# ADC5G_PLL.net
KiCad netlist of a schematic drawn in Altium Designer
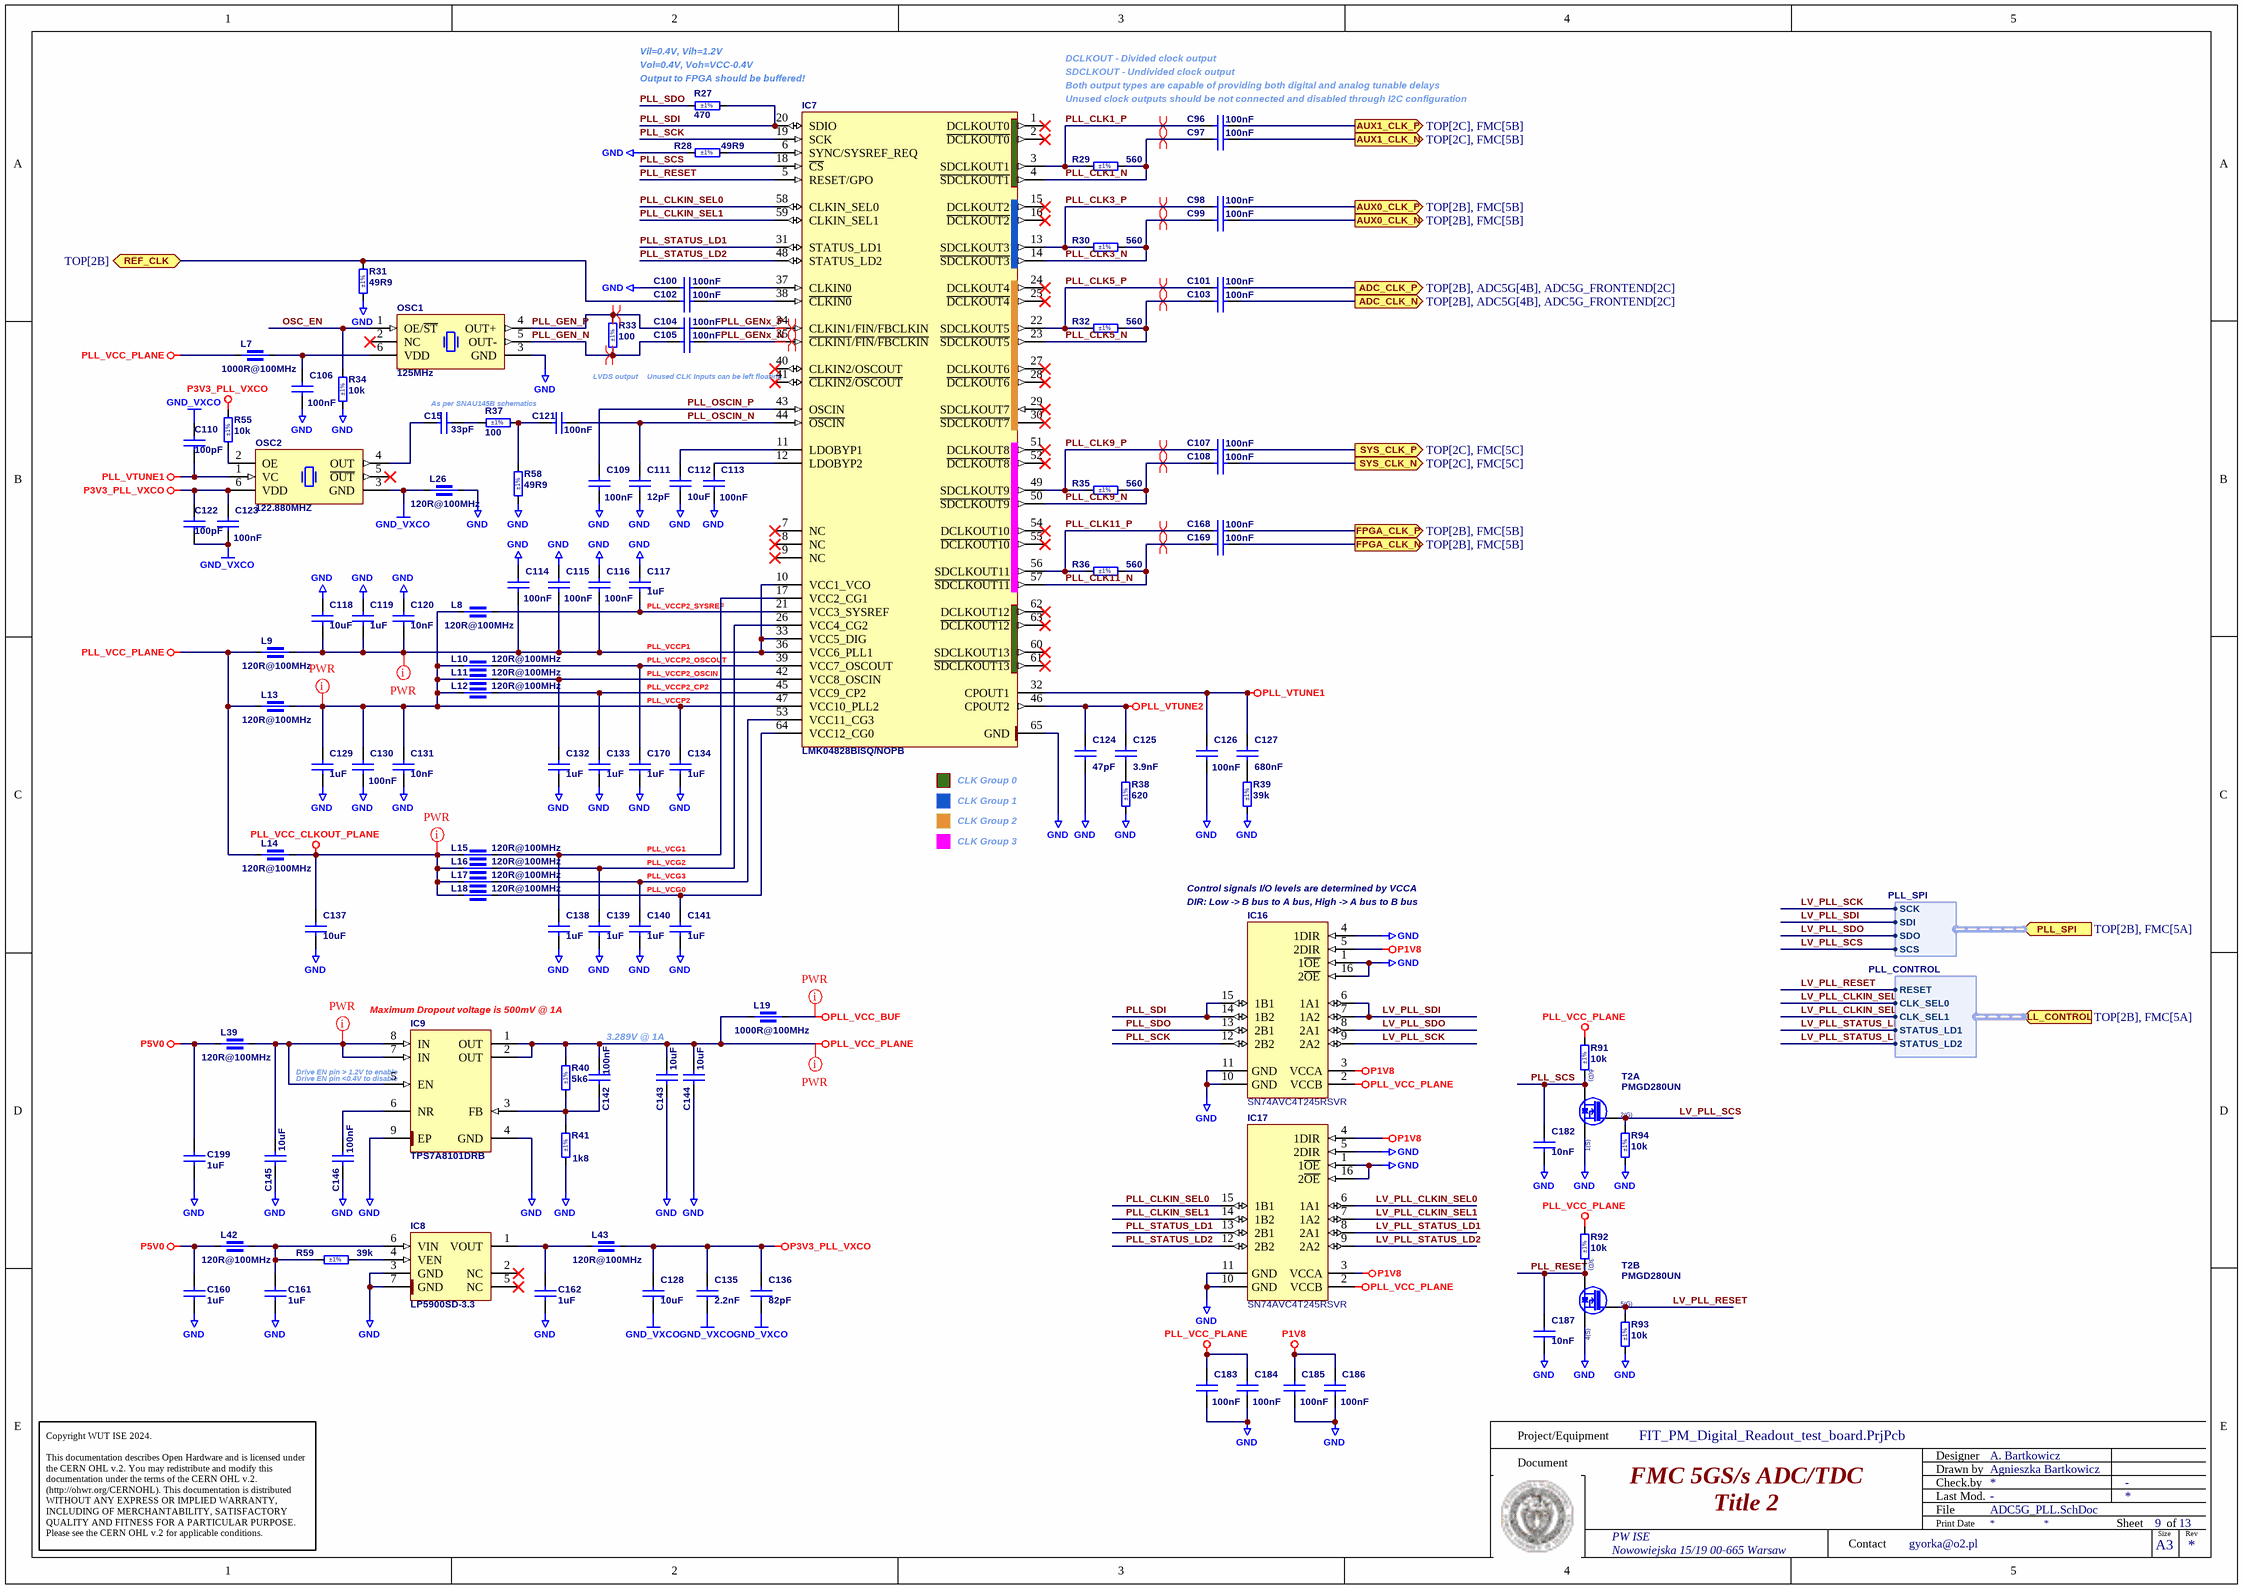
[diagram p0: ADC5G_PLL.SchDoc]

(export (version "E")
  (design (tool "Eeschema 10.0.6"))
  (components
    (comp (ref "C15")
      (value "33pF")
      (footprint "CAPC1005X61N")
      (description "Non-polarised capacitor")
      (fields
        (field (name "PART NUMBER") "CC0402_33PF_50V_1%_NP0_JOHANSON_R07S")
        (field (name "VOLTAGE") "50V")
        (field (name "AUTHOR") "CERN DEM BC")
      )
      (libsource (lib "Capacitors") (part "Capacitor - non polarized"))
    )
    (comp (ref "C96")
      (value "100nF")
      (footprint "CAPC1005X55N")
      (description "Non-polarised capacitor")
      (fields
        (field (name "PART NUMBER") "CC0402_100NF_16V_10%_X5R")
        (field (name "VOLTAGE") "16V")
        (field (name "AUTHOR") "CERN DEM JLC")
      )
      (libsource (lib "Capacitors") (part "Capacitor - non polarized"))
    )
    (comp (ref "C97")
      (value "100nF")
      (footprint "CAPC1005X55N")
      (description "Non-polarised capacitor")
      (fields
        (field (name "PART NUMBER") "CC0402_100NF_16V_10%_X5R")
        (field (name "VOLTAGE") "16V")
        (field (name "AUTHOR") "CERN DEM JLC")
      )
      (libsource (lib "Capacitors") (part "Capacitor - non polarized"))
    )
    (comp (ref "C98")
      (value "100nF")
      (footprint "CAPC1005X55N")
      (description "Non-polarised capacitor")
      (fields
        (field (name "PART NUMBER") "CC0402_100NF_16V_10%_X5R")
        (field (name "VOLTAGE") "16V")
        (field (name "AUTHOR") "CERN DEM JLC")
      )
      (libsource (lib "Capacitors") (part "Capacitor - non polarized"))
    )
    (comp (ref "C99")
      (value "100nF")
      (footprint "CAPC1005X55N")
      (description "Non-polarised capacitor")
      (fields
        (field (name "PART NUMBER") "CC0402_100NF_16V_10%_X5R")
        (field (name "VOLTAGE") "16V")
        (field (name "AUTHOR") "CERN DEM JLC")
      )
      (libsource (lib "Capacitors") (part "Capacitor - non polarized"))
    )
    (comp (ref "C100")
      (value "100nF")
      (footprint "CAPC1005X55N")
      (description "Non-polarised capacitor")
      (fields
        (field (name "PART NUMBER") "CC0402_100NF_16V_10%_X5R")
        (field (name "VOLTAGE") "16V")
        (field (name "AUTHOR") "CERN DEM JLC")
      )
      (libsource (lib "Capacitors") (part "Capacitor - non polarized"))
    )
    (comp (ref "C101")
      (value "100nF")
      (footprint "CAPC1005X55N")
      (description "Non-polarised capacitor")
      (fields
        (field (name "PART NUMBER") "CC0402_100NF_16V_10%_X5R")
        (field (name "VOLTAGE") "16V")
        (field (name "AUTHOR") "CERN DEM JLC")
      )
      (libsource (lib "Capacitors") (part "Capacitor - non polarized"))
    )
    (comp (ref "C102")
      (value "100nF")
      (footprint "CAPC1005X55N")
      (description "Non-polarised capacitor")
      (fields
        (field (name "PART NUMBER") "CC0402_100NF_16V_10%_X5R")
        (field (name "VOLTAGE") "16V")
        (field (name "AUTHOR") "CERN DEM JLC")
      )
      (libsource (lib "Capacitors") (part "Capacitor - non polarized"))
    )
    (comp (ref "C103")
      (value "100nF")
      (footprint "CAPC1005X55N")
      (description "Non-polarised capacitor")
      (fields
        (field (name "PART NUMBER") "CC0402_100NF_16V_10%_X5R")
        (field (name "VOLTAGE") "16V")
        (field (name "AUTHOR") "CERN DEM JLC")
      )
      (libsource (lib "Capacitors") (part "Capacitor - non polarized"))
    )
    (comp (ref "C104")
      (value "100nF")
      (footprint "CAPC1005X55N")
      (description "Non-polarised capacitor")
      (fields
        (field (name "PART NUMBER") "CC0402_100NF_16V_10%_X5R")
        (field (name "VOLTAGE") "16V")
        (field (name "AUTHOR") "CERN DEM JLC")
      )
      (libsource (lib "Capacitors") (part "Capacitor - non polarized"))
    )
    (comp (ref "C105")
      (value "100nF")
      (footprint "CAPC1005X55N")
      (description "Non-polarised capacitor")
      (fields
        (field (name "PART NUMBER") "CC0402_100NF_16V_10%_X5R")
        (field (name "VOLTAGE") "16V")
        (field (name "AUTHOR") "CERN DEM JLC")
      )
      (libsource (lib "Capacitors") (part "Capacitor - non polarized"))
    )
    (comp (ref "C106")
      (value "100nF")
      (footprint "CAPC1005X55N")
      (description "Non-polarised capacitor")
      (fields
        (field (name "PART NUMBER") "CC0402_100NF_16V_10%_X5R")
        (field (name "VOLTAGE") "16V")
        (field (name "AUTHOR") "CERN DEM JLC")
      )
      (libsource (lib "Capacitors") (part "Capacitor - non polarized"))
    )
    (comp (ref "C107")
      (value "100nF")
      (footprint "CAPC1005X55N")
      (description "Non-polarised capacitor")
      (fields
        (field (name "PART NUMBER") "CC0402_100NF_16V_10%_X5R")
        (field (name "VOLTAGE") "16V")
        (field (name "AUTHOR") "CERN DEM JLC")
      )
      (libsource (lib "Capacitors") (part "Capacitor - non polarized"))
    )
    (comp (ref "C108")
      (value "100nF")
      (footprint "CAPC1005X55N")
      (description "Non-polarised capacitor")
      (fields
        (field (name "PART NUMBER") "CC0402_100NF_16V_10%_X5R")
        (field (name "VOLTAGE") "16V")
        (field (name "AUTHOR") "CERN DEM JLC")
      )
      (libsource (lib "Capacitors") (part "Capacitor - non polarized"))
    )
    (comp (ref "C109")
      (value "100nF")
      (footprint "CAPC1005X55N")
      (description "Non-polarised capacitor")
      (fields
        (field (name "PART NUMBER") "CC0402_100NF_16V_10%_X5R")
        (field (name "VOLTAGE") "16V")
        (field (name "AUTHOR") "CERN DEM JLC")
      )
      (libsource (lib "Capacitors") (part "Capacitor - non polarized"))
    )
    (comp (ref "C110")
      (value "100pF")
      (footprint "CAPC1005X55N")
      (description "Non-polarised capacitor")
      (fields
        (field (name "PART NUMBER") "CC0402_100PF_25V_1%_C0G")
        (field (name "VOLTAGE") "25V")
        (field (name "AUTHOR") "CERN DEM HF")
      )
      (libsource (lib "Capacitors") (part "Capacitor - non polarized"))
    )
    (comp (ref "C111")
      (value "12pF")
      (footprint "CAPC1005X61N")
      (description "Non-polarised capacitor")
      (fields
        (field (name "PART NUMBER") "CC0402_12PF_50V_1%_NP0_JOHANSON_R07S")
        (field (name "VOLTAGE") "50V")
        (field (name "AUTHOR") "CERN DEM BC")
      )
      (libsource (lib "Capacitors") (part "Capacitor - non polarized"))
    )
    (comp (ref "C112")
      (value "10uF")
      (footprint "CAPC1608X90N")
      (description "Non-polarised capacitor")
      (fields
        (field (name "PART NUMBER") "CC0603_10UF_16V_10%_X5R_MURATA_GRT188R61C106KE13")
        (field (name "VOLTAGE") "16V")
        (field (name "AUTHOR") "CERN DEM HF")
      )
      (libsource (lib "Capacitors") (part "Capacitor - non polarized"))
    )
    (comp (ref "C113")
      (value "100nF")
      (footprint "CAPC1005X55N")
      (description "Non-polarised capacitor")
      (fields
        (field (name "PART NUMBER") "CC0402_100NF_16V_10%_X5R")
        (field (name "VOLTAGE") "16V")
        (field (name "AUTHOR") "CERN DEM JLC")
      )
      (libsource (lib "Capacitors") (part "Capacitor - non polarized"))
    )
    (comp (ref "C114")
      (value "100nF")
      (footprint "CAPC1005X55N")
      (description "Non-polarised capacitor")
      (fields
        (field (name "PART NUMBER") "CC0402_100NF_16V_10%_X5R")
        (field (name "VOLTAGE") "16V")
        (field (name "AUTHOR") "CERN DEM JLC")
      )
      (libsource (lib "Capacitors") (part "Capacitor - non polarized"))
    )
    (comp (ref "C115")
      (value "100nF")
      (footprint "CAPC1005X55N")
      (description "Non-polarised capacitor")
      (fields
        (field (name "PART NUMBER") "CC0402_100NF_16V_10%_X5R")
        (field (name "VOLTAGE") "16V")
        (field (name "AUTHOR") "CERN DEM JLC")
      )
      (libsource (lib "Capacitors") (part "Capacitor - non polarized"))
    )
    (comp (ref "C116")
      (value "100nF")
      (footprint "CAPC1005X55N")
      (description "Non-polarised capacitor")
      (fields
        (field (name "PART NUMBER") "CC0402_100NF_16V_10%_X5R")
        (field (name "VOLTAGE") "16V")
        (field (name "AUTHOR") "CERN DEM JLC")
      )
      (libsource (lib "Capacitors") (part "Capacitor - non polarized"))
    )
    (comp (ref "C117")
      (value "1uF")
      (footprint "CAPC1005X55N")
      (description "Non-polarised capacitor")
      (fields
        (field (name "PART NUMBER") "CC0402_1UF_16V_10%_X5R")
        (field (name "VOLTAGE") "16V")
        (field (name "AUTHOR") "CERN DEM JLC")
      )
      (libsource (lib "Capacitors") (part "Capacitor - non polarized"))
    )
    (comp (ref "C118")
      (value "10uF")
      (footprint "CAPC1608X90N")
      (description "Non-polarised capacitor")
      (fields
        (field (name "PART NUMBER") "CC0603_10UF_16V_10%_X5R_MURATA_GRT188R61C106KE13")
        (field (name "VOLTAGE") "16V")
        (field (name "AUTHOR") "CERN DEM HF")
      )
      (libsource (lib "Capacitors") (part "Capacitor - non polarized"))
    )
    (comp (ref "C119")
      (value "1uF")
      (footprint "CAPC1005X55N")
      (description "Non-polarised capacitor")
      (fields
        (field (name "PART NUMBER") "CC0402_1UF_16V_10%_X5R")
        (field (name "VOLTAGE") "16V")
        (field (name "AUTHOR") "CERN DEM JLC")
      )
      (libsource (lib "Capacitors") (part "Capacitor - non polarized"))
    )
    (comp (ref "C120")
      (value "10nF")
      (footprint "CAPC1005X55N")
      (description "Non-polarised capacitor")
      (fields
        (field (name "PART NUMBER") "CC0402_10NF_50V_10%_X7R")
        (field (name "VOLTAGE") "50V")
        (field (name "AUTHOR") "CERN DEM MR")
      )
      (libsource (lib "Capacitors") (part "Capacitor - non polarized"))
    )
    (comp (ref "C121")
      (value "100nF")
      (footprint "CAPC1005X55N")
      (description "Non-polarised capacitor")
      (fields
        (field (name "PART NUMBER") "CC0402_100NF_16V_10%_X5R")
        (field (name "VOLTAGE") "16V")
        (field (name "AUTHOR") "CERN DEM JLC")
      )
      (libsource (lib "Capacitors") (part "Capacitor - non polarized"))
    )
    (comp (ref "C122")
      (value "100pF")
      (footprint "CAPC1005X55N")
      (description "Non-polarised capacitor")
      (fields
        (field (name "PART NUMBER") "CC0402_100PF_25V_1%_C0G")
        (field (name "VOLTAGE") "25V")
        (field (name "AUTHOR") "CERN DEM HF")
      )
      (libsource (lib "Capacitors") (part "Capacitor - non polarized"))
    )
    (comp (ref "C123")
      (value "100nF")
      (footprint "CAPC1005X55N")
      (description "Non-polarised capacitor")
      (fields
        (field (name "PART NUMBER") "CC0402_100NF_16V_10%_X5R")
        (field (name "VOLTAGE") "16V")
        (field (name "AUTHOR") "CERN DEM JLC")
      )
      (libsource (lib "Capacitors") (part "Capacitor - non polarized"))
    )
    (comp (ref "C124")
      (value "47pF")
      (footprint "CAPC1005X55N")
      (description "Non-polarised capacitor")
      (fields
        (field (name "PART NUMBER") "CC0402_47PF_50V_1%_C0G_MURATA_GJM1555C1H470FB01D")
        (field (name "VOLTAGE") "50V")
        (field (name "AUTHOR") "CERN DEM BC")
      )
      (libsource (lib "Capacitors") (part "Capacitor - non polarized"))
    )
    (comp (ref "C125")
      (value "3.9nF")
      (footprint "CAPC1005X55N")
      (description "Non-polarised capacitor")
      (fields
        (field (name "PART NUMBER") "CC0402_3.9NF_50V_5%_X7R")
        (field (name "VOLTAGE") "50V")
        (field (name "AUTHOR") "CERN DEM BC")
      )
      (libsource (lib "Capacitors") (part "Capacitor - non polarized"))
    )
    (comp (ref "C126")
      (value "100nF")
      (footprint "CAPC1005X55N")
      (description "Non-polarised capacitor")
      (fields
        (field (name "PART NUMBER") "CC0402_100NF_16V_10%_X5R")
        (field (name "VOLTAGE") "16V")
        (field (name "AUTHOR") "CERN DEM JLC")
      )
      (libsource (lib "Capacitors") (part "Capacitor - non polarized"))
    )
    (comp (ref "C127")
      (value "680nF")
      (footprint "CAPC1005X55N")
      (description "Non-polarised capacitor")
      (fields
        (field (name "PART NUMBER") "CC0402_680NF_10V_10%_X5R")
        (field (name "VOLTAGE") "10V")
        (field (name "AUTHOR") "CERN DEM BC")
      )
      (libsource (lib "Capacitors") (part "Capacitor - non polarized"))
    )
    (comp (ref "C128")
      (value "10uF")
      (footprint "CAPC1608X90N")
      (description "Non-polarised capacitor")
      (fields
        (field (name "PART NUMBER") "CC0603_10UF_16V_10%_X5R_MURATA_GRT188R61C106KE13")
        (field (name "VOLTAGE") "16V")
        (field (name "AUTHOR") "CERN DEM HF")
      )
      (libsource (lib "Capacitors") (part "Capacitor - non polarized"))
    )
    (comp (ref "C129")
      (value "1uF")
      (footprint "CAPC1005X55N")
      (description "Non-polarised capacitor")
      (fields
        (field (name "PART NUMBER") "CC0402_1UF_16V_10%_X5R")
        (field (name "VOLTAGE") "16V")
        (field (name "AUTHOR") "CERN DEM JLC")
      )
      (libsource (lib "Capacitors") (part "Capacitor - non polarized"))
    )
    (comp (ref "C130")
      (value "100nF")
      (footprint "CAPC1005X55N")
      (description "Non-polarised capacitor")
      (fields
        (field (name "PART NUMBER") "CC0402_100NF_16V_10%_X5R")
        (field (name "VOLTAGE") "16V")
        (field (name "AUTHOR") "CERN DEM JLC")
      )
      (libsource (lib "Capacitors") (part "Capacitor - non polarized"))
    )
    (comp (ref "C131")
      (value "10nF")
      (footprint "CAPC1005X55N")
      (description "Non-polarised capacitor")
      (fields
        (field (name "PART NUMBER") "CC0402_10NF_50V_10%_X7R")
        (field (name "VOLTAGE") "50V")
        (field (name "AUTHOR") "CERN DEM MR")
      )
      (libsource (lib "Capacitors") (part "Capacitor - non polarized"))
    )
    (comp (ref "C132")
      (value "1uF")
      (footprint "CAPC1005X55N")
      (description "Non-polarised capacitor")
      (fields
        (field (name "PART NUMBER") "CC0402_1UF_16V_10%_X5R")
        (field (name "VOLTAGE") "16V")
        (field (name "AUTHOR") "CERN DEM JLC")
      )
      (libsource (lib "Capacitors") (part "Capacitor - non polarized"))
    )
    (comp (ref "C133")
      (value "1uF")
      (footprint "CAPC1005X55N")
      (description "Non-polarised capacitor")
      (fields
        (field (name "PART NUMBER") "CC0402_1UF_16V_10%_X5R")
        (field (name "VOLTAGE") "16V")
        (field (name "AUTHOR") "CERN DEM JLC")
      )
      (libsource (lib "Capacitors") (part "Capacitor - non polarized"))
    )
    (comp (ref "C134")
      (value "1uF")
      (footprint "CAPC1005X55N")
      (description "Non-polarised capacitor")
      (fields
        (field (name "PART NUMBER") "CC0402_1UF_16V_10%_X5R")
        (field (name "VOLTAGE") "16V")
        (field (name "AUTHOR") "CERN DEM JLC")
      )
      (libsource (lib "Capacitors") (part "Capacitor - non polarized"))
    )
    (comp (ref "C135")
      (value "2.2nF")
      (footprint "CAPC1005X55N")
      (description "Non-polarised capacitor")
      (fields
        (field (name "PART NUMBER") "CC0402_2.2NF_50V_10%_X7R")
        (field (name "VOLTAGE") "50V")
        (field (name "AUTHOR") "CERN DEM JLC")
      )
      (libsource (lib "Capacitors") (part "Capacitor - non polarized"))
    )
    (comp (ref "C136")
      (value "82pF")
      (footprint "CAPC1005X55N")
      (description "Non-polarised capacitor")
      (fields
        (field (name "PART NUMBER") "CC0402_82PF_25V_1%_C0G_KEMET_HiQ-CBR")
        (field (name "VOLTAGE") "25V")
        (field (name "AUTHOR") "CERN DEM MR")
      )
      (libsource (lib "Capacitors") (part "Capacitor - non polarized"))
    )
    (comp (ref "C137")
      (value "10uF")
      (footprint "CAPC1608X90N")
      (description "Non-polarised capacitor")
      (fields
        (field (name "PART NUMBER") "CC0603_10UF_16V_10%_X5R_MURATA_GRT188R61C106KE13")
        (field (name "VOLTAGE") "16V")
        (field (name "AUTHOR") "CERN DEM HF")
      )
      (libsource (lib "Capacitors") (part "Capacitor - non polarized"))
    )
    (comp (ref "C138")
      (value "1uF")
      (footprint "CAPC1005X55N")
      (description "Non-polarised capacitor")
      (fields
        (field (name "PART NUMBER") "CC0402_1UF_16V_10%_X5R")
        (field (name "VOLTAGE") "16V")
        (field (name "AUTHOR") "CERN DEM JLC")
      )
      (libsource (lib "Capacitors") (part "Capacitor - non polarized"))
    )
    (comp (ref "C139")
      (value "1uF")
      (footprint "CAPC1005X55N")
      (description "Non-polarised capacitor")
      (fields
        (field (name "PART NUMBER") "CC0402_1UF_16V_10%_X5R")
        (field (name "VOLTAGE") "16V")
        (field (name "AUTHOR") "CERN DEM JLC")
      )
      (libsource (lib "Capacitors") (part "Capacitor - non polarized"))
    )
    (comp (ref "C140")
      (value "1uF")
      (footprint "CAPC1005X55N")
      (description "Non-polarised capacitor")
      (fields
        (field (name "PART NUMBER") "CC0402_1UF_16V_10%_X5R")
        (field (name "VOLTAGE") "16V")
        (field (name "AUTHOR") "CERN DEM JLC")
      )
      (libsource (lib "Capacitors") (part "Capacitor - non polarized"))
    )
    (comp (ref "C141")
      (value "1uF")
      (footprint "CAPC1005X55N")
      (description "Non-polarised capacitor")
      (fields
        (field (name "PART NUMBER") "CC0402_1UF_16V_10%_X5R")
        (field (name "VOLTAGE") "16V")
        (field (name "AUTHOR") "CERN DEM JLC")
      )
      (libsource (lib "Capacitors") (part "Capacitor - non polarized"))
    )
    (comp (ref "C142")
      (value "100nF")
      (footprint "CAPC1005X55N")
      (description "Non-polarised capacitor")
      (fields
        (field (name "PART NUMBER") "CC0402_100NF_16V_10%_X5R")
        (field (name "VOLTAGE") "16V")
        (field (name "AUTHOR") "CERN DEM JLC")
      )
      (libsource (lib "Capacitors") (part "Capacitor - non polarized"))
    )
    (comp (ref "C143")
      (value "10uF")
      (footprint "CAPC1608X90N")
      (description "Non-polarised capacitor")
      (fields
        (field (name "PART NUMBER") "CC0603_10UF_16V_10%_X5R_MURATA_GRT188R61C106KE13")
        (field (name "VOLTAGE") "16V")
        (field (name "AUTHOR") "CERN DEM HF")
      )
      (libsource (lib "Capacitors") (part "Capacitor - non polarized"))
    )
    (comp (ref "C144")
      (value "10uF")
      (footprint "CAPC1608X90N")
      (description "Non-polarised capacitor")
      (fields
        (field (name "PART NUMBER") "CC0603_10UF_16V_10%_X5R_MURATA_GRT188R61C106KE13")
        (field (name "VOLTAGE") "16V")
        (field (name "AUTHOR") "CERN DEM HF")
      )
      (libsource (lib "Capacitors") (part "Capacitor - non polarized"))
    )
    (comp (ref "C145")
      (value "10uF")
      (footprint "CAPC1608X90N")
      (description "Non-polarised capacitor")
      (fields
        (field (name "PART NUMBER") "CC0603_10UF_16V_10%_X5R_MURATA_GRT188R61C106KE13")
        (field (name "VOLTAGE") "16V")
        (field (name "AUTHOR") "CERN DEM HF")
      )
      (libsource (lib "Capacitors") (part "Capacitor - non polarized"))
    )
    (comp (ref "C146")
      (value "100nF")
      (footprint "CAPC1005X55N")
      (description "Non-polarised capacitor")
      (fields
        (field (name "PART NUMBER") "CC0402_100NF_16V_10%_X5R")
        (field (name "VOLTAGE") "16V")
        (field (name "AUTHOR") "CERN DEM JLC")
      )
      (libsource (lib "Capacitors") (part "Capacitor - non polarized"))
    )
    (comp (ref "C160")
      (value "1uF")
      (footprint "CAPC1005X55N")
      (description "Non-polarised capacitor")
      (fields
        (field (name "PART NUMBER") "CC0402_1UF_16V_10%_X5R")
        (field (name "VOLTAGE") "16V")
        (field (name "AUTHOR") "CERN DEM JLC")
      )
      (libsource (lib "Capacitors") (part "Capacitor - non polarized"))
    )
    (comp (ref "C161")
      (value "1uF")
      (footprint "CAPC1005X55N")
      (description "Non-polarised capacitor")
      (fields
        (field (name "PART NUMBER") "CC0402_1UF_16V_10%_X5R")
        (field (name "VOLTAGE") "16V")
        (field (name "AUTHOR") "CERN DEM JLC")
      )
      (libsource (lib "Capacitors") (part "Capacitor - non polarized"))
    )
    (comp (ref "C162")
      (value "1uF")
      (footprint "CAPC1005X55N")
      (description "Non-polarised capacitor")
      (fields
        (field (name "PART NUMBER") "CC0402_1UF_16V_10%_X5R")
        (field (name "VOLTAGE") "16V")
        (field (name "AUTHOR") "CERN DEM JLC")
      )
      (libsource (lib "Capacitors") (part "Capacitor - non polarized"))
    )
    (comp (ref "C168")
      (value "100nF")
      (footprint "CAPC1005X55N")
      (description "Non-polarised capacitor")
      (fields
        (field (name "PART NUMBER") "CC0402_100NF_16V_10%_X5R")
        (field (name "VOLTAGE") "16V")
        (field (name "AUTHOR") "CERN DEM JLC")
      )
      (libsource (lib "Capacitors") (part "Capacitor - non polarized"))
    )
    (comp (ref "C169")
      (value "100nF")
      (footprint "CAPC1005X55N")
      (description "Non-polarised capacitor")
      (fields
        (field (name "PART NUMBER") "CC0402_100NF_16V_10%_X5R")
        (field (name "VOLTAGE") "16V")
        (field (name "AUTHOR") "CERN DEM JLC")
      )
      (libsource (lib "Capacitors") (part "Capacitor - non polarized"))
    )
    (comp (ref "C170")
      (value "1uF")
      (footprint "CAPC1005X55N")
      (description "Non-polarised capacitor")
      (fields
        (field (name "PART NUMBER") "CC0402_1UF_16V_10%_X5R")
        (field (name "VOLTAGE") "16V")
        (field (name "AUTHOR") "CERN DEM JLC")
      )
      (libsource (lib "Capacitors") (part "Capacitor - non polarized"))
    )
    (comp (ref "C182")
      (value "10nF")
      (footprint "CAPC1005X55N")
      (description "Non-polarised capacitor")
      (fields
        (field (name "PART NUMBER") "CC0402_10NF_50V_10%_X7R")
        (field (name "VOLTAGE") "50V")
        (field (name "AUTHOR") "CERN DEM MR")
      )
      (libsource (lib "Capacitors") (part "Capacitor - non polarized"))
    )
    (comp (ref "C183")
      (value "100nF")
      (footprint "CAPC1005X55N")
      (description "Non-polarised capacitor")
      (fields
        (field (name "PART NUMBER") "CC0402_100NF_16V_10%_X5R")
        (field (name "VOLTAGE") "16V")
        (field (name "AUTHOR") "CERN DEM JLC")
      )
      (libsource (lib "Capacitors") (part "Capacitor - non polarized"))
    )
    (comp (ref "C184")
      (value "100nF")
      (footprint "CAPC1005X55N")
      (description "Non-polarised capacitor")
      (fields
        (field (name "PART NUMBER") "CC0402_100NF_16V_10%_X5R")
        (field (name "VOLTAGE") "16V")
        (field (name "AUTHOR") "CERN DEM JLC")
      )
      (libsource (lib "Capacitors") (part "Capacitor - non polarized"))
    )
    (comp (ref "C185")
      (value "100nF")
      (footprint "CAPC1005X55N")
      (description "Non-polarised capacitor")
      (fields
        (field (name "PART NUMBER") "CC0402_100NF_16V_10%_X5R")
        (field (name "VOLTAGE") "16V")
        (field (name "AUTHOR") "CERN DEM JLC")
      )
      (libsource (lib "Capacitors") (part "Capacitor - non polarized"))
    )
    (comp (ref "C186")
      (value "100nF")
      (footprint "CAPC1005X55N")
      (description "Non-polarised capacitor")
      (fields
        (field (name "PART NUMBER") "CC0402_100NF_16V_10%_X5R")
        (field (name "VOLTAGE") "16V")
        (field (name "AUTHOR") "CERN DEM JLC")
      )
      (libsource (lib "Capacitors") (part "Capacitor - non polarized"))
    )
    (comp (ref "C187")
      (value "10nF")
      (footprint "CAPC1005X55N")
      (description "Non-polarised capacitor")
      (fields
        (field (name "PART NUMBER") "CC0402_10NF_50V_10%_X7R")
        (field (name "VOLTAGE") "50V")
        (field (name "AUTHOR") "CERN DEM MR")
      )
      (libsource (lib "Capacitors") (part "Capacitor - non polarized"))
    )
    (comp (ref "C199")
      (value "1uF")
      (footprint "CAPC1005X55N")
      (description "Non-polarised capacitor")
      (fields
        (field (name "PART NUMBER") "CC0402_1UF_16V_10%_X5R")
        (field (name "VOLTAGE") "16V")
        (field (name "AUTHOR") "CERN DEM JLC")
      )
      (libsource (lib "Capacitors") (part "Capacitor - non polarized"))
    )
    (comp (ref "IC7")
      (value "LMK04828BISQ/NOPB")
      (footprint "QFN50P900X900X80-65N-S730")
      (description "Ultra Low-Noise Clock Jitter Cleaner with Dual Loop PLLs")
      (fields
        (field (name "MANUFACTURER") "TEXAS INSTRUMENTS")
        (field (name "MANUFACTURER PART NUMBER") "LMK04828BISQ")
        (field (name "AUTHOR") "CERN DEM MR")
      )
      (libsource (lib "ICs And Semiconductors") (part "LMK04828"))
    )
    (comp (ref "IC8")
      (value "LP5900SD-3.3")
      (footprint "SON65P250X220X80-7N-R85X130")
      (description "Ultra Low Noise, 150 mA Linear Regulator for RF/Analog Circuits Requires No Bypass Capacitor")
      (fields (field (name "MANUFACTURER") "TEXAS INSTRUMENTS") (field (name "AUTHOR") "CERN DEM JLC"))
      (libsource (lib "ICs And Semiconductors") (part "LP5900SD"))
    )
    (comp (ref "IC9")
      (value "TPS7A8101DRB")
      (footprint "TEXAS_DRB(S-PVSON-N8)")
      (description "0.8V to 6V, 1A, Low-Noise, Wide-Bandwidth, High PSRR, Low-Dropout Linear Regulator")
      (fields (field (name "MANUFACTURER") "TEXAS INSTRUMENTS") (field (name "AUTHOR") "CERN DEM BC"))
      (libsource (lib "ICs And Semiconductors") (part "TPS7A8101DRB"))
    )
    (comp (ref "IC16")
      (value "SN74AVC4T245RSVR")
      (footprint "QFN40P180X260X55-16N")
      (description "4-Bit Dual-Supply Bus Transceiver with Configurable Voltage Translation and 3-State Output")
      (fields (field (name "MANUFACTURER") "TEXAS INSTRUMENTS") (field (name "AUTHOR") "CERN DEM JLC"))
      (libsource (lib "ICs And Semiconductors") (part "744T245_a"))
    )
    (comp (ref "IC17")
      (value "SN74AVC4T245RSVR")
      (footprint "QFN40P180X260X55-16N")
      (description "4-Bit Dual-Supply Bus Transceiver with Configurable Voltage Translation and 3-State Output")
      (fields (field (name "MANUFACTURER") "TEXAS INSTRUMENTS") (field (name "AUTHOR") "CERN DEM JLC"))
      (libsource (lib "ICs And Semiconductors") (part "744T245_a"))
    )
    (comp (ref "L7")
      (value "1000R@100MHz")
      (footprint "INDC1608X95N")
      (fields
        (field (name "PART NUMBER") "IND0603_MURATA_BLM18KG102SN1")
        (field (name "POWER") "1A")
        (field (name "TOLERANCE") "±25%")
        (field (name "AUTHOR") "CERN DEM HF")
      )
      (libsource (lib "Inductors & Transformers") (part "Ferrite Bead"))
    )
    (comp (ref "L8")
      (value "120R@100MHz")
      (footprint "INDC1005X55N")
      (fields
        (field (name "PART NUMBER") "IND0402_MURATA_BLM15PX121SN1D")
        (field (name "POWER") "2A")
        (field (name "TOLERANCE") "±25%")
        (field (name "AUTHOR") "CERN DEM JMW")
      )
      (libsource (lib "Inductors & Transformers") (part "Ferrite Bead"))
    )
    (comp (ref "L9")
      (value "120R@100MHz")
      (footprint "INDC1005X55N")
      (fields
        (field (name "PART NUMBER") "IND0402_MURATA_BLM15PX121SN1D")
        (field (name "POWER") "2A")
        (field (name "TOLERANCE") "±25%")
        (field (name "AUTHOR") "CERN DEM JMW")
      )
      (libsource (lib "Inductors & Transformers") (part "Ferrite Bead"))
    )
    (comp (ref "L10")
      (value "120R@100MHz")
      (footprint "INDC1005X55N")
      (fields
        (field (name "PART NUMBER") "IND0402_MURATA_BLM15PX121SN1D")
        (field (name "POWER") "2A")
        (field (name "TOLERANCE") "±25%")
        (field (name "AUTHOR") "CERN DEM JMW")
      )
      (libsource (lib "Inductors & Transformers") (part "Ferrite Bead"))
    )
    (comp (ref "L11")
      (value "120R@100MHz")
      (footprint "INDC1005X55N")
      (fields
        (field (name "PART NUMBER") "IND0402_MURATA_BLM15PX121SN1D")
        (field (name "POWER") "2A")
        (field (name "TOLERANCE") "±25%")
        (field (name "AUTHOR") "CERN DEM JMW")
      )
      (libsource (lib "Inductors & Transformers") (part "Ferrite Bead"))
    )
    (comp (ref "L12")
      (value "120R@100MHz")
      (footprint "INDC1005X55N")
      (fields
        (field (name "PART NUMBER") "IND0402_MURATA_BLM15PX121SN1D")
        (field (name "POWER") "2A")
        (field (name "TOLERANCE") "±25%")
        (field (name "AUTHOR") "CERN DEM JMW")
      )
      (libsource (lib "Inductors & Transformers") (part "Ferrite Bead"))
    )
    (comp (ref "L13")
      (value "120R@100MHz")
      (footprint "INDC1005X55N")
      (fields
        (field (name "PART NUMBER") "IND0402_MURATA_BLM15PX121SN1D")
        (field (name "POWER") "2A")
        (field (name "TOLERANCE") "±25%")
        (field (name "AUTHOR") "CERN DEM JMW")
      )
      (libsource (lib "Inductors & Transformers") (part "Ferrite Bead"))
    )
    (comp (ref "L14")
      (value "120R@100MHz")
      (footprint "INDC1005X55N")
      (fields
        (field (name "PART NUMBER") "IND0402_MURATA_BLM15PX121SN1D")
        (field (name "POWER") "2A")
        (field (name "TOLERANCE") "±25%")
        (field (name "AUTHOR") "CERN DEM JMW")
      )
      (libsource (lib "Inductors & Transformers") (part "Ferrite Bead"))
    )
    (comp (ref "L15")
      (value "120R@100MHz")
      (footprint "INDC1005X55N")
      (fields
        (field (name "PART NUMBER") "IND0402_MURATA_BLM15PX121SN1D")
        (field (name "POWER") "2A")
        (field (name "TOLERANCE") "±25%")
        (field (name "AUTHOR") "CERN DEM JMW")
      )
      (libsource (lib "Inductors & Transformers") (part "Ferrite Bead"))
    )
    (comp (ref "L16")
      (value "120R@100MHz")
      (footprint "INDC1005X55N")
      (fields
        (field (name "PART NUMBER") "IND0402_MURATA_BLM15PX121SN1D")
        (field (name "POWER") "2A")
        (field (name "TOLERANCE") "±25%")
        (field (name "AUTHOR") "CERN DEM JMW")
      )
      (libsource (lib "Inductors & Transformers") (part "Ferrite Bead"))
    )
    (comp (ref "L17")
      (value "120R@100MHz")
      (footprint "INDC1005X55N")
      (fields
        (field (name "PART NUMBER") "IND0402_MURATA_BLM15PX121SN1D")
        (field (name "POWER") "2A")
        (field (name "TOLERANCE") "±25%")
        (field (name "AUTHOR") "CERN DEM JMW")
      )
      (libsource (lib "Inductors & Transformers") (part "Ferrite Bead"))
    )
    (comp (ref "L18")
      (value "120R@100MHz")
      (footprint "INDC1005X55N")
      (fields
        (field (name "PART NUMBER") "IND0402_MURATA_BLM15PX121SN1D")
        (field (name "POWER") "2A")
        (field (name "TOLERANCE") "±25%")
        (field (name "AUTHOR") "CERN DEM JMW")
      )
      (libsource (lib "Inductors & Transformers") (part "Ferrite Bead"))
    )
    (comp (ref "L19")
      (value "1000R@100MHz")
      (footprint "INDC1608X95N")
      (fields
        (field (name "PART NUMBER") "IND0603_MURATA_BLM18KG102SN1")
        (field (name "POWER") "1A")
        (field (name "TOLERANCE") "±25%")
        (field (name "AUTHOR") "CERN DEM HF")
      )
      (libsource (lib "Inductors & Transformers") (part "Ferrite Bead"))
    )
    (comp (ref "L26")
      (value "120R@100MHz")
      (footprint "INDC1005X55N")
      (fields
        (field (name "PART NUMBER") "IND0402_MURATA_BLM15PX121SN1D")
        (field (name "POWER") "2A")
        (field (name "TOLERANCE") "±25%")
        (field (name "AUTHOR") "CERN DEM JMW")
      )
      (libsource (lib "Inductors & Transformers") (part "Ferrite Bead"))
    )
    (comp (ref "L39")
      (value "120R@100MHz")
      (footprint "INDC1005X55N")
      (fields
        (field (name "PART NUMBER") "IND0402_MURATA_BLM15PX121SN1D")
        (field (name "POWER") "2A")
        (field (name "TOLERANCE") "±25%")
        (field (name "AUTHOR") "CERN DEM JMW")
      )
      (libsource (lib "Inductors & Transformers") (part "Ferrite Bead"))
    )
    (comp (ref "L42")
      (value "120R@100MHz")
      (footprint "INDC1005X55N")
      (fields
        (field (name "PART NUMBER") "IND0402_MURATA_BLM15PX121SN1D")
        (field (name "POWER") "2A")
        (field (name "TOLERANCE") "±25%")
        (field (name "AUTHOR") "CERN DEM JMW")
      )
      (libsource (lib "Inductors & Transformers") (part "Ferrite Bead"))
    )
    (comp (ref "L43")
      (value "120R@100MHz")
      (footprint "INDC1005X55N")
      (fields
        (field (name "PART NUMBER") "IND0402_MURATA_BLM15PX121SN1D")
        (field (name "POWER") "2A")
        (field (name "TOLERANCE") "±25%")
        (field (name "AUTHOR") "CERN DEM JMW")
      )
      (libsource (lib "Inductors & Transformers") (part "Ferrite Bead"))
    )
    (comp (ref "OSC1")
      (value "125MHz")
      (footprint "OSC_SI-TIME_SIT9121-C")
      (description "Standard Frequency Differential Oscillator")
      (fields
        (field (name "PART NUMBER") "OSC_125MHZ_SI-TIME_SIT9121AI-2C2-33E125.000000")
        (field (name "MANUFACTURER") "SI TIME")
        (field (name "AUTHOR") "CERN DEM HF")
      )
      (libsource (lib "ICs And Semiconductors") (part "Oscillator SI-TIME_SIT9121"))
    )
    (comp (ref "OSC2")
      (value "122.880MHZ")
      (footprint "OSCSC254P500X700X190-6N")
      (description "Programmable - High Performance SMD VCXO")
      (fields
        (field (name "PART NUMBER") "OSC_122.880MHZ_ABRACON_ASG-D-V-A-122.880MHZ")
        (field (name "MANUFACTURER") "ABRACON")
        (field (name "AUTHOR") "CERN DEM HF")
      )
      (libsource (lib "ICs And Semiconductors") (part "Oscillator ABRACON_ASG-D-V"))
    )
    (comp (ref "R27")
      (value "470")
      (footprint "RESC1005X40N")
      (description "Resistor - 1%")
      (fields
        (field (name "TOLERANCE") "±1%")
        (field (name "PART NUMBER") "R0402_470R_1%_0.0625W_100PPM")
        (field (name "POWER") "0.0625W")
        (field (name "AUTHOR") "CERN DEM JLC")
      )
      (libsource (lib "Resistors") (part "Resistor - 1%"))
    )
    (comp (ref "R28")
      (value "49R9")
      (footprint "RESC1005X40N")
      (description "Resistor - 1%")
      (fields
        (field (name "TOLERANCE") "±1%")
        (field (name "PART NUMBER") "R0402_49R9_1%_0.0625W_100PPM")
        (field (name "POWER") "0.0625W")
        (field (name "AUTHOR") "CERN DEM JLC")
      )
      (libsource (lib "Resistors") (part "Resistor - 1%"))
    )
    (comp (ref "R29")
      (value "560")
      (footprint "RESC1005X40N")
      (description "Resistor - 1%")
      (fields
        (field (name "TOLERANCE") "±1%")
        (field (name "PART NUMBER") "R0402_560R_1%_0.0625W_100PPM")
        (field (name "POWER") "0.0625W")
        (field (name "AUTHOR") "CERN DEM JLC")
      )
      (libsource (lib "Resistors") (part "Resistor - 1%"))
    )
    (comp (ref "R30")
      (value "560")
      (footprint "RESC1005X40N")
      (description "Resistor - 1%")
      (fields
        (field (name "TOLERANCE") "±1%")
        (field (name "PART NUMBER") "R0402_560R_1%_0.0625W_100PPM")
        (field (name "POWER") "0.0625W")
        (field (name "AUTHOR") "CERN DEM JLC")
      )
      (libsource (lib "Resistors") (part "Resistor - 1%"))
    )
    (comp (ref "R31")
      (value "49R9")
      (footprint "RESC1005X40N")
      (description "Resistor - 1%")
      (fields
        (field (name "TOLERANCE") "±1%")
        (field (name "PART NUMBER") "R0402_49R9_1%_0.0625W_100PPM")
        (field (name "POWER") "0.0625W")
        (field (name "AUTHOR") "CERN DEM JLC")
      )
      (libsource (lib "Resistors") (part "Resistor - 1%"))
    )
    (comp (ref "R32")
      (value "560")
      (footprint "RESC1005X40N")
      (description "Resistor - 1%")
      (fields
        (field (name "TOLERANCE") "±1%")
        (field (name "PART NUMBER") "R0402_560R_1%_0.0625W_100PPM")
        (field (name "POWER") "0.0625W")
        (field (name "AUTHOR") "CERN DEM JLC")
      )
      (libsource (lib "Resistors") (part "Resistor - 1%"))
    )
    (comp (ref "R33")
      (value "100")
      (footprint "RESC1005X40N")
      (description "Resistor - 1%")
      (fields
        (field (name "TOLERANCE") "±1%")
        (field (name "PART NUMBER") "R0402_100R_1%_0.0625W_100PPM")
        (field (name "POWER") "0.0625W")
        (field (name "AUTHOR") "CERN DEM JLC")
      )
      (libsource (lib "Resistors") (part "Resistor - 1%"))
    )
    (comp (ref "R34")
      (value "10k")
      (footprint "RESC1005X40N")
      (description "Resistor - 1%")
      (fields
        (field (name "TOLERANCE") "±1%")
        (field (name "PART NUMBER") "R0402_10K_1%_0.0625W_100PPM")
        (field (name "POWER") "0.0625W")
        (field (name "AUTHOR") "CERN DEM JLC")
      )
      (libsource (lib "Resistors") (part "Resistor - 1%"))
    )
    (comp (ref "R35")
      (value "560")
      (footprint "RESC1005X40N")
      (description "Resistor - 1%")
      (fields
        (field (name "TOLERANCE") "±1%")
        (field (name "PART NUMBER") "R0402_560R_1%_0.0625W_100PPM")
        (field (name "POWER") "0.0625W")
        (field (name "AUTHOR") "CERN DEM JLC")
      )
      (libsource (lib "Resistors") (part "Resistor - 1%"))
    )
    (comp (ref "R36")
      (value "560")
      (footprint "RESC1005X40N")
      (description "Resistor - 1%")
      (fields
        (field (name "TOLERANCE") "±1%")
        (field (name "PART NUMBER") "R0402_560R_1%_0.0625W_100PPM")
        (field (name "POWER") "0.0625W")
        (field (name "AUTHOR") "CERN DEM JLC")
      )
      (libsource (lib "Resistors") (part "Resistor - 1%"))
    )
    (comp (ref "R37")
      (value "100")
      (footprint "RESC1005X40N")
      (description "Resistor - 1%")
      (fields
        (field (name "TOLERANCE") "±1%")
        (field (name "PART NUMBER") "R0402_100R_1%_0.0625W_100PPM")
        (field (name "POWER") "0.0625W")
        (field (name "AUTHOR") "CERN DEM JLC")
      )
      (libsource (lib "Resistors") (part "Resistor - 1%"))
    )
    (comp (ref "R38")
      (value "620")
      (footprint "RESC1005X40N")
      (description "Resistor - 1%")
      (fields
        (field (name "TOLERANCE") "±1%")
        (field (name "PART NUMBER") "R0402_620R_1%_0.0625W_100PPM")
        (field (name "POWER") "0.0625W")
        (field (name "AUTHOR") "CERN DEM JLC")
      )
      (libsource (lib "Resistors") (part "Resistor - 1%"))
    )
    (comp (ref "R39")
      (value "39k")
      (footprint "RESC1005X40N")
      (description "Resistor - 1%")
      (fields
        (field (name "TOLERANCE") "±1%")
        (field (name "PART NUMBER") "R0402_39K_1%_0.0625W_100PPM")
        (field (name "POWER") "0.0625W")
        (field (name "AUTHOR") "CERN DEM JLC")
      )
      (libsource (lib "Resistors") (part "Resistor - 1%"))
    )
    (comp (ref "R40")
      (value "5k6")
      (footprint "RESC1005X40N")
      (description "Resistor - 1%")
      (fields
        (field (name "TOLERANCE") "±1%")
        (field (name "PART NUMBER") "R0402_5K6_1%_0.0625W_100PPM")
        (field (name "POWER") "0.0625W")
        (field (name "AUTHOR") "CERN DEM JLC")
      )
      (libsource (lib "Resistors") (part "Resistor - 1%"))
    )
    (comp (ref "R41")
      (value "1k8")
      (footprint "RESC1005X40N")
      (description "Resistor - 1%")
      (fields
        (field (name "TOLERANCE") "±1%")
        (field (name "PART NUMBER") "R0402_1K8_1%_0.0625W_100PPM")
        (field (name "POWER") "0.0625W")
        (field (name "AUTHOR") "CERN DEM JLC")
      )
      (libsource (lib "Resistors") (part "Resistor - 1%"))
    )
    (comp (ref "R55")
      (value "10k")
      (footprint "RESC1005X40N")
      (description "Resistor - 1%")
      (fields
        (field (name "TOLERANCE") "±1%")
        (field (name "PART NUMBER") "R0402_10K_1%_0.0625W_100PPM")
        (field (name "POWER") "0.0625W")
        (field (name "AUTHOR") "CERN DEM JLC")
      )
      (libsource (lib "Resistors") (part "Resistor - 1%"))
    )
    (comp (ref "R58")
      (value "49R9")
      (footprint "RESC1005X40N")
      (description "Resistor - 1%")
      (fields
        (field (name "TOLERANCE") "±1%")
        (field (name "PART NUMBER") "R0402_49R9_1%_0.0625W_100PPM")
        (field (name "POWER") "0.0625W")
        (field (name "AUTHOR") "CERN DEM JLC")
      )
      (libsource (lib "Resistors") (part "Resistor - 1%"))
    )
    (comp (ref "R59")
      (value "39k")
      (footprint "RESC1005X40N")
      (description "Resistor - 1%")
      (fields
        (field (name "TOLERANCE") "±1%")
        (field (name "PART NUMBER") "R0402_39K_1%_0.0625W_100PPM")
        (field (name "POWER") "0.0625W")
        (field (name "AUTHOR") "CERN DEM JLC")
      )
      (libsource (lib "Resistors") (part "Resistor - 1%"))
    )
    (comp (ref "R91")
      (value "10k")
      (footprint "RESC1005X40N")
      (description "Resistor - 1%")
      (fields
        (field (name "TOLERANCE") "±1%")
        (field (name "PART NUMBER") "R0402_10K_1%_0.0625W_100PPM")
        (field (name "POWER") "0.0625W")
        (field (name "AUTHOR") "CERN DEM JLC")
      )
      (libsource (lib "Resistors") (part "Resistor - 1%"))
    )
    (comp (ref "R92")
      (value "10k")
      (footprint "RESC1005X40N")
      (description "Resistor - 1%")
      (fields
        (field (name "TOLERANCE") "±1%")
        (field (name "PART NUMBER") "R0402_10K_1%_0.0625W_100PPM")
        (field (name "POWER") "0.0625W")
        (field (name "AUTHOR") "CERN DEM JLC")
      )
      (libsource (lib "Resistors") (part "Resistor - 1%"))
    )
    (comp (ref "R93")
      (value "10k")
      (footprint "RESC1005X40N")
      (description "Resistor - 1%")
      (fields
        (field (name "TOLERANCE") "±1%")
        (field (name "PART NUMBER") "R0402_10K_1%_0.0625W_100PPM")
        (field (name "POWER") "0.0625W")
        (field (name "AUTHOR") "CERN DEM JLC")
      )
      (libsource (lib "Resistors") (part "Resistor - 1%"))
    )
    (comp (ref "R94")
      (value "10k")
      (footprint "RESC1005X40N")
      (description "Resistor - 1%")
      (fields
        (field (name "TOLERANCE") "±1%")
        (field (name "PART NUMBER") "R0402_10K_1%_0.0625W_100PPM")
        (field (name "POWER") "0.0625W")
        (field (name "AUTHOR") "CERN DEM JLC")
      )
      (libsource (lib "Resistors") (part "Resistor - 1%"))
    )
    (comp (ref "T2")
      (value "PMGD280UN")
      (footprint "SOT65P210X110-6N")
      (description "Dual N-Channel micro TrenchMOS™ Ultra Low Level FET")
      (fields (field (name "MANUFACTURER") "NXP SEMICONDUCTORS") (field (name "AUTHOR") "CERN DEM JLC"))
      (libsource (lib "") (part "PMGD280UN_1"))
    )
  )
  (nets
    (net (code "3") (name "/ADC_CLK_N") (class "Default")
      (node (ref "C103") (pin "2") (pinfunction "2_2") (pintype "passive"))
    )
    (net (code "4") (name "/ADC_CLK_P") (class "Default")
      (node (ref "C101") (pin "2") (pinfunction "2_2") (pintype "passive"))
    )
    (net (code "5") (name "/AUX0_CLK_N") (class "Default")
      (node (ref "C99") (pin "2") (pinfunction "2_2") (pintype "passive"))
    )
    (net (code "6") (name "/AUX0_CLK_P") (class "Default")
      (node (ref "C98") (pin "2") (pinfunction "2_2") (pintype "passive"))
    )
    (net (code "7") (name "/AUX1_CLK_N") (class "Default")
      (node (ref "C97") (pin "2") (pinfunction "2_2") (pintype "passive"))
    )
    (net (code "8") (name "/AUX1_CLK_P") (class "Default")
      (node (ref "C96") (pin "2") (pinfunction "2_2") (pintype "passive"))
    )
    (net (code "9") (name "/FPGA_CLK_N") (class "Default")
      (node (ref "C169") (pin "2") (pinfunction "2_2") (pintype "passive"))
    )
    (net (code "10") (name "/FPGA_CLK_P") (class "Default")
      (node (ref "C168") (pin "2") (pinfunction "2_2") (pintype "passive"))
    )
    (net (code "11") (name "/LV_PLL_CLKIN_SEL0") (class "Default")
      (node (ref "IC17") (pin "6") (pinfunction "1A1_6") (pintype "bidirectional"))
    )
    (net (code "12") (name "/LV_PLL_CLKIN_SEL1") (class "Default")
      (node (ref "IC17") (pin "7") (pinfunction "1A2_7") (pintype "bidirectional"))
    )
    (net (code "13") (name "/LV_PLL_RESET") (class "Default")
      (node (ref "R93") (pin "2") (pinfunction "2_2") (pintype "passive"))
      (node (ref "T2") (pin "5") (pinfunction "G_5") (pintype "passive"))
    )
    (net (code "14") (name "/LV_PLL_SCK") (class "Default")
      (node (ref "IC16") (pin "9") (pinfunction "2A2_9") (pintype "bidirectional"))
    )
    (net (code "15") (name "/LV_PLL_SCS") (class "Default")
      (node (ref "R94") (pin "2") (pinfunction "2_2") (pintype "passive"))
      (node (ref "T2") (pin "2") (pinfunction "G_2") (pintype "passive"))
    )
    (net (code "16") (name "/LV_PLL_SDI") (class "Default")
      (node (ref "IC16") (pin "6") (pinfunction "1A1_6") (pintype "bidirectional"))
      (node (ref "IC16") (pin "7") (pinfunction "1A2_7") (pintype "bidirectional"))
    )
    (net (code "17") (name "/LV_PLL_SDO") (class "Default")
      (node (ref "IC16") (pin "8") (pinfunction "2A1_8") (pintype "bidirectional"))
    )
    (net (code "18") (name "/LV_PLL_STATUS_LD1") (class "Default")
      (node (ref "IC17") (pin "8") (pinfunction "2A1_8") (pintype "bidirectional"))
    )
    (net (code "19") (name "/LV_PLL_STATUS_LD2") (class "Default")
      (node (ref "IC17") (pin "9") (pinfunction "2A2_9") (pintype "bidirectional"))
    )
    (net (code "20") (name "/OSC_EN") (class "Default")
      (node (ref "OSC1") (pin "1") (pinfunction "OE/~{ST}_1") (pintype "input"))
      (node (ref "R34") (pin "2") (pinfunction "2_2") (pintype "passive"))
    )
    (net (code "21") (name "/PLL_CLK1_N") (class "Default")
      (node (ref "C97") (pin "1") (pinfunction "1_1") (pintype "passive"))
      (node (ref "IC7") (pin "4") (pinfunction "~{SDCLKOUT1}_4") (pintype "output"))
      (node (ref "R29") (pin "2") (pinfunction "2_2") (pintype "passive"))
    )
    (net (code "22") (name "/PLL_CLK1_P") (class "Default")
      (node (ref "C96") (pin "1") (pinfunction "1_1") (pintype "passive"))
      (node (ref "IC7") (pin "3") (pinfunction "SDCLKOUT1_3") (pintype "output"))
      (node (ref "R29") (pin "1") (pinfunction "1_1") (pintype "passive"))
    )
    (net (code "23") (name "/PLL_CLK3_N") (class "Default")
      (node (ref "C99") (pin "1") (pinfunction "1_1") (pintype "passive"))
      (node (ref "IC7") (pin "14") (pinfunction "~{SDCLKOUT3}_14") (pintype "output"))
      (node (ref "R30") (pin "2") (pinfunction "2_2") (pintype "passive"))
    )
    (net (code "24") (name "/PLL_CLK3_P") (class "Default")
      (node (ref "C98") (pin "1") (pinfunction "1_1") (pintype "passive"))
      (node (ref "IC7") (pin "13") (pinfunction "SDCLKOUT3_13") (pintype "output"))
      (node (ref "R30") (pin "1") (pinfunction "1_1") (pintype "passive"))
    )
    (net (code "25") (name "/PLL_CLK5_N") (class "Default")
      (node (ref "C103") (pin "1") (pinfunction "1_1") (pintype "passive"))
      (node (ref "IC7") (pin "23") (pinfunction "~{SDCLKOUT5}_23") (pintype "output"))
      (node (ref "R32") (pin "2") (pinfunction "2_2") (pintype "passive"))
    )
    (net (code "26") (name "/PLL_CLK5_P") (class "Default")
      (node (ref "C101") (pin "1") (pinfunction "1_1") (pintype "passive"))
      (node (ref "IC7") (pin "22") (pinfunction "SDCLKOUT5_22") (pintype "output"))
      (node (ref "R32") (pin "1") (pinfunction "1_1") (pintype "passive"))
    )
    (net (code "27") (name "/PLL_CLK9_N") (class "Default")
      (node (ref "C108") (pin "1") (pinfunction "1_1") (pintype "passive"))
      (node (ref "IC7") (pin "50") (pinfunction "~{SDCLKOUT9}_50") (pintype "output"))
      (node (ref "R35") (pin "2") (pinfunction "2_2") (pintype "passive"))
    )
    (net (code "28") (name "/PLL_CLK9_P") (class "Default")
      (node (ref "C107") (pin "1") (pinfunction "1_1") (pintype "passive"))
      (node (ref "IC7") (pin "49") (pinfunction "SDCLKOUT9_49") (pintype "output"))
      (node (ref "R35") (pin "1") (pinfunction "1_1") (pintype "passive"))
    )
    (net (code "29") (name "/PLL_CLK11_N") (class "Default")
      (node (ref "C169") (pin "1") (pinfunction "1_1") (pintype "passive"))
      (node (ref "IC7") (pin "57") (pinfunction "~{SDCLKOUT11}_57") (pintype "output"))
      (node (ref "R36") (pin "2") (pinfunction "2_2") (pintype "passive"))
    )
    (net (code "30") (name "/PLL_CLK11_P") (class "Default")
      (node (ref "C168") (pin "1") (pinfunction "1_1") (pintype "passive"))
      (node (ref "IC7") (pin "56") (pinfunction "SDCLKOUT11_56") (pintype "output"))
      (node (ref "R36") (pin "1") (pinfunction "1_1") (pintype "passive"))
    )
    (net (code "31") (name "/PLL_CLKIN_SEL0") (class "Default")
      (node (ref "IC17") (pin "15") (pinfunction "1B1_15") (pintype "bidirectional"))
      (node (ref "IC7") (pin "58") (pinfunction "CLKIN_SEL0_58") (pintype "bidirectional"))
    )
    (net (code "32") (name "/PLL_CLKIN_SEL1") (class "Default")
      (node (ref "IC17") (pin "14") (pinfunction "1B2_14") (pintype "bidirectional"))
      (node (ref "IC7") (pin "59") (pinfunction "CLKIN_SEL1_59") (pintype "bidirectional"))
    )
    (net (code "33") (name "/PLL_GEN_N") (class "Default")
      (node (ref "C105") (pin "1") (pinfunction "1_1") (pintype "passive"))
      (node (ref "OSC1") (pin "5") (pinfunction "OUT-_5") (pintype "output"))
      (node (ref "R33") (pin "1") (pinfunction "1_1") (pintype "passive"))
    )
    (net (code "34") (name "/PLL_GEN_P") (class "Default")
      (node (ref "C104") (pin "1") (pinfunction "1_1") (pintype "passive"))
      (node (ref "OSC1") (pin "4") (pinfunction "OUT+_4") (pintype "output"))
      (node (ref "R33") (pin "2") (pinfunction "2_2") (pintype "passive"))
    )
    (net (code "35") (name "/PLL_GENx_N") (class "Default")
      (node (ref "C105") (pin "2") (pinfunction "2_2") (pintype "passive"))
      (node (ref "IC7") (pin "35") (pinfunction "~{CLKIN1}/~{FIN}/~{FBCLKIN}_35") (pintype "input"))
    )
    (net (code "36") (name "/PLL_GENx_P") (class "Default")
      (node (ref "C104") (pin "2") (pinfunction "2_2") (pintype "passive"))
      (node (ref "IC7") (pin "34") (pinfunction "CLKIN1/FIN/FBCLKIN_34") (pintype "input"))
    )
    (net (code "37") (name "/PLL_OSCIN_N") (class "Default")
      (node (ref "C111") (pin "2") (pinfunction "2_2") (pintype "passive"))
      (node (ref "C121") (pin "1") (pinfunction "1_1") (pintype "passive"))
      (node (ref "IC7") (pin "44") (pinfunction "~{OSCIN}_44") (pintype "input"))
    )
    (net (code "38") (name "/PLL_OSCIN_P") (class "Default")
      (node (ref "C109") (pin "2") (pinfunction "2_2") (pintype "passive"))
      (node (ref "IC7") (pin "43") (pinfunction "OSCIN_43") (pintype "input"))
    )
    (net (code "39") (name "/PLL_RESET") (class "Default")
      (node (ref "C187") (pin "2") (pinfunction "2_2") (pintype "passive"))
      (node (ref "IC7") (pin "5") (pinfunction "RESET/GPO_5") (pintype "input"))
      (node (ref "R92") (pin "1") (pinfunction "1_1") (pintype "passive"))
      (node (ref "T2") (pin "3") (pinfunction "D_3") (pintype "passive"))
    )
    (net (code "40") (name "/PLL_SCK") (class "Default")
      (node (ref "IC16") (pin "12") (pinfunction "2B2_12") (pintype "bidirectional"))
      (node (ref "IC7") (pin "19") (pinfunction "SCK_19") (pintype "input"))
    )
    (net (code "41") (name "/PLL_SCS") (class "Default")
      (node (ref "C182") (pin "2") (pinfunction "2_2") (pintype "passive"))
      (node (ref "IC7") (pin "18") (pinfunction "~{CS}_18") (pintype "input"))
      (node (ref "R91") (pin "1") (pinfunction "1_1") (pintype "passive"))
      (node (ref "T2") (pin "6") (pinfunction "D_6") (pintype "passive"))
    )
    (net (code "42") (name "/PLL_SDI") (class "Default")
      (node (ref "IC16") (pin "14") (pinfunction "1B2_14") (pintype "bidirectional"))
      (node (ref "IC16") (pin "15") (pinfunction "1B1_15") (pintype "bidirectional"))
      (node (ref "IC7") (pin "20") (pinfunction "SDIO_20") (pintype "bidirectional"))
      (node (ref "R27") (pin "2") (pinfunction "2_2") (pintype "passive"))
    )
    (net (code "43") (name "/PLL_SDO") (class "Default")
      (node (ref "IC16") (pin "13") (pinfunction "2B1_13") (pintype "bidirectional"))
      (node (ref "R27") (pin "1") (pinfunction "1_1") (pintype "passive"))
    )
    (net (code "44") (name "/PLL_STATUS_LD1") (class "Default")
      (node (ref "IC17") (pin "13") (pinfunction "2B1_13") (pintype "bidirectional"))
      (node (ref "IC7") (pin "31") (pinfunction "STATUS_LD1_31") (pintype "bidirectional"))
    )
    (net (code "45") (name "/PLL_STATUS_LD2") (class "Default")
      (node (ref "IC17") (pin "12") (pinfunction "2B2_12") (pintype "bidirectional"))
      (node (ref "IC7") (pin "48") (pinfunction "STATUS_LD2_48") (pintype "bidirectional"))
    )
    (net (code "46") (name "/PLL_VCCP1") (class "Default")
      (node (ref "C114") (pin "1") (pinfunction "1_1") (pintype "passive"))
      (node (ref "C115") (pin "1") (pinfunction "1_1") (pintype "passive"))
      (node (ref "C116") (pin "1") (pinfunction "1_1") (pintype "passive"))
      (node (ref "C118") (pin "1") (pinfunction "1_1") (pintype "passive"))
      (node (ref "C119") (pin "1") (pinfunction "1_1") (pintype "passive"))
      (node (ref "C120") (pin "1") (pinfunction "1_1") (pintype "passive"))
      (node (ref "IC7") (pin "10") (pinfunction "VCC1_VCO_10") (pintype "power_in"))
      (node (ref "IC7") (pin "33") (pinfunction "VCC5_DIG_33") (pintype "power_in"))
      (node (ref "IC7") (pin "36") (pinfunction "VCC6_PLL1_36") (pintype "power_in"))
      (node (ref "L9") (pin "2") (pinfunction "2_2") (pintype "passive"))
    )
    (net (code "47") (name "/PLL_VCCP2") (class "Default")
      (node (ref "C129") (pin "2") (pinfunction "2_2") (pintype "passive"))
      (node (ref "C130") (pin "2") (pinfunction "2_2") (pintype "passive"))
      (node (ref "C131") (pin "2") (pinfunction "2_2") (pintype "passive"))
      (node (ref "C134") (pin "2") (pinfunction "2_2") (pintype "passive"))
      (node (ref "IC7") (pin "47") (pinfunction "VCC10_PLL2_47") (pintype "power_in"))
      (node (ref "L10") (pin "1") (pinfunction "1_1") (pintype "passive"))
      (node (ref "L11") (pin "1") (pinfunction "1_1") (pintype "passive"))
      (node (ref "L12") (pin "1") (pinfunction "1_1") (pintype "passive"))
      (node (ref "L13") (pin "2") (pinfunction "2_2") (pintype "passive"))
      (node (ref "L8") (pin "1") (pinfunction "1_1") (pintype "passive"))
    )
    (net (code "48") (name "/PLL_VCCP2_CP2") (class "Default")
      (node (ref "C133") (pin "2") (pinfunction "2_2") (pintype "passive"))
      (node (ref "IC7") (pin "45") (pinfunction "VCC9_CP2_45") (pintype "power_in"))
      (node (ref "L12") (pin "2") (pinfunction "2_2") (pintype "passive"))
    )
    (net (code "49") (name "/PLL_VCCP2_OSCIN") (class "Default")
      (node (ref "C132") (pin "2") (pinfunction "2_2") (pintype "passive"))
      (node (ref "IC7") (pin "42") (pinfunction "VCC8_OSCIN_42") (pintype "power_in"))
      (node (ref "L11") (pin "2") (pinfunction "2_2") (pintype "passive"))
    )
    (net (code "50") (name "/PLL_VCCP2_OSCOUT") (class "Default")
      (node (ref "C170") (pin "2") (pinfunction "2_2") (pintype "passive"))
      (node (ref "IC7") (pin "39") (pinfunction "VCC7_OSCOUT_39") (pintype "power_in"))
      (node (ref "L10") (pin "2") (pinfunction "2_2") (pintype "passive"))
    )
    (net (code "51") (name "/PLL_VCCP2_SYSREF") (class "Default")
      (node (ref "C117") (pin "1") (pinfunction "1_1") (pintype "passive"))
      (node (ref "IC7") (pin "21") (pinfunction "VCC3_SYSREF_21") (pintype "power_in"))
      (node (ref "L8") (pin "2") (pinfunction "2_2") (pintype "passive"))
    )
    (net (code "52") (name "/PLL_VCG0") (class "Default")
      (node (ref "C141") (pin "2") (pinfunction "2_2") (pintype "passive"))
      (node (ref "IC7") (pin "64") (pinfunction "VCC12_CG0_64") (pintype "power_in"))
      (node (ref "L18") (pin "2") (pinfunction "2_2") (pintype "passive"))
    )
    (net (code "53") (name "/PLL_VCG1") (class "Default")
      (node (ref "C138") (pin "2") (pinfunction "2_2") (pintype "passive"))
      (node (ref "IC7") (pin "17") (pinfunction "VCC2_CG1_17") (pintype "power_in"))
      (node (ref "L15") (pin "2") (pinfunction "2_2") (pintype "passive"))
    )
    (net (code "54") (name "/PLL_VCG2") (class "Default")
      (node (ref "C139") (pin "2") (pinfunction "2_2") (pintype "passive"))
      (node (ref "IC7") (pin "26") (pinfunction "VCC4_CG2_26") (pintype "power_in"))
      (node (ref "L16") (pin "2") (pinfunction "2_2") (pintype "passive"))
    )
    (net (code "55") (name "/PLL_VCG3") (class "Default")
      (node (ref "C140") (pin "2") (pinfunction "2_2") (pintype "passive"))
      (node (ref "IC7") (pin "53") (pinfunction "VCC11_CG3_53") (pintype "power_in"))
      (node (ref "L17") (pin "2") (pinfunction "2_2") (pintype "passive"))
    )
    (net (code "56") (name "/REF_CLK") (class "Default")
      (node (ref "C102") (pin "1") (pinfunction "1_1") (pintype "passive"))
      (node (ref "R31") (pin "2") (pinfunction "2_2") (pintype "passive"))
    )
    (net (code "57") (name "/SYS_CLK_N") (class "Default")
      (node (ref "C108") (pin "2") (pinfunction "2_2") (pintype "passive"))
    )
    (net (code "58") (name "/SYS_CLK_P") (class "Default")
      (node (ref "C107") (pin "2") (pinfunction "2_2") (pintype "passive"))
    )
    (net (code "61") (name "GND") (class "Default")
      (node (ref "C100") (pin "1") (pinfunction "1_1") (pintype "passive"))
      (node (ref "C106") (pin "1") (pinfunction "1_1") (pintype "passive"))
      (node (ref "C109") (pin "1") (pinfunction "1_1") (pintype "passive"))
      (node (ref "C111") (pin "1") (pinfunction "1_1") (pintype "passive"))
      (node (ref "C112") (pin "1") (pinfunction "1_1") (pintype "passive"))
      (node (ref "C113") (pin "1") (pinfunction "1_1") (pintype "passive"))
      (node (ref "C114") (pin "2") (pinfunction "2_2") (pintype "passive"))
      (node (ref "C115") (pin "2") (pinfunction "2_2") (pintype "passive"))
      (node (ref "C116") (pin "2") (pinfunction "2_2") (pintype "passive"))
      (node (ref "C117") (pin "2") (pinfunction "2_2") (pintype "passive"))
      (node (ref "C118") (pin "2") (pinfunction "2_2") (pintype "passive"))
      (node (ref "C119") (pin "2") (pinfunction "2_2") (pintype "passive"))
      (node (ref "C120") (pin "2") (pinfunction "2_2") (pintype "passive"))
      (node (ref "C124") (pin "1") (pinfunction "1_1") (pintype "passive"))
      (node (ref "C126") (pin "1") (pinfunction "1_1") (pintype "passive"))
      (node (ref "C129") (pin "1") (pinfunction "1_1") (pintype "passive"))
      (node (ref "C130") (pin "1") (pinfunction "1_1") (pintype "passive"))
      (node (ref "C131") (pin "1") (pinfunction "1_1") (pintype "passive"))
      (node (ref "C132") (pin "1") (pinfunction "1_1") (pintype "passive"))
      (node (ref "C133") (pin "1") (pinfunction "1_1") (pintype "passive"))
      (node (ref "C134") (pin "1") (pinfunction "1_1") (pintype "passive"))
      (node (ref "C137") (pin "1") (pinfunction "1_1") (pintype "passive"))
      (node (ref "C138") (pin "1") (pinfunction "1_1") (pintype "passive"))
      (node (ref "C139") (pin "1") (pinfunction "1_1") (pintype "passive"))
      (node (ref "C140") (pin "1") (pinfunction "1_1") (pintype "passive"))
      (node (ref "C141") (pin "1") (pinfunction "1_1") (pintype "passive"))
      (node (ref "C143") (pin "1") (pinfunction "1_1") (pintype "passive"))
      (node (ref "C144") (pin "1") (pinfunction "1_1") (pintype "passive"))
      (node (ref "C145") (pin "1") (pinfunction "1_1") (pintype "passive"))
      (node (ref "C146") (pin "1") (pinfunction "1_1") (pintype "passive"))
      (node (ref "C160") (pin "1") (pinfunction "1_1") (pintype "passive"))
      (node (ref "C161") (pin "1") (pinfunction "1_1") (pintype "passive"))
      (node (ref "C162") (pin "1") (pinfunction "1_1") (pintype "passive"))
      (node (ref "C170") (pin "1") (pinfunction "1_1") (pintype "passive"))
      (node (ref "C182") (pin "1") (pinfunction "1_1") (pintype "passive"))
      (node (ref "C183") (pin "1") (pinfunction "1_1") (pintype "passive"))
      (node (ref "C184") (pin "1") (pinfunction "1_1") (pintype "passive"))
      (node (ref "C185") (pin "1") (pinfunction "1_1") (pintype "passive"))
      (node (ref "C186") (pin "1") (pinfunction "1_1") (pintype "passive"))
      (node (ref "C187") (pin "1") (pinfunction "1_1") (pintype "passive"))
      (node (ref "C199") (pin "1") (pinfunction "1_1") (pintype "passive"))
      (node (ref "IC16") (pin "1") (pinfunction "1~{OE}_1") (pintype "input"))
      (node (ref "IC16") (pin "10") (pinfunction "GND_10") (pintype "power_in"))
      (node (ref "IC16") (pin "11") (pinfunction "GND_11") (pintype "power_in"))
      (node (ref "IC16") (pin "16") (pinfunction "2~{OE}_16") (pintype "input"))
      (node (ref "IC16") (pin "4") (pinfunction "1DIR_4") (pintype "input"))
      (node (ref "IC17") (pin "1") (pinfunction "1~{OE}_1") (pintype "input"))
      (node (ref "IC17") (pin "10") (pinfunction "GND_10") (pintype "power_in"))
      (node (ref "IC17") (pin "11") (pinfunction "GND_11") (pintype "power_in"))
      (node (ref "IC17") (pin "16") (pinfunction "2~{OE}_16") (pintype "input"))
      (node (ref "IC17") (pin "5") (pinfunction "2DIR_5") (pintype "input"))
      (node (ref "IC7") (pin "65") (pinfunction "GND_65") (pintype "power_in"))
      (node (ref "IC8") (pin "3") (pinfunction "GND_3") (pintype "power_in"))
      (node (ref "IC8") (pin "7") (pinfunction "GND_7") (pintype "power_in"))
      (node (ref "IC9") (pin "4") (pinfunction "GND_4") (pintype "power_in"))
      (node (ref "IC9") (pin "9") (pinfunction "EP_9") (pintype "power_in"))
      (node (ref "L26") (pin "2") (pinfunction "2_2") (pintype "passive"))
      (node (ref "OSC1") (pin "3") (pinfunction "GND_3") (pintype "power_in"))
      (node (ref "R28") (pin "1") (pinfunction "1_1") (pintype "passive"))
      (node (ref "R31") (pin "1") (pinfunction "1_1") (pintype "passive"))
      (node (ref "R34") (pin "1") (pinfunction "1_1") (pintype "passive"))
      (node (ref "R38") (pin "1") (pinfunction "1_1") (pintype "passive"))
      (node (ref "R39") (pin "1") (pinfunction "1_1") (pintype "passive"))
      (node (ref "R41") (pin "1") (pinfunction "1_1") (pintype "passive"))
      (node (ref "R58") (pin "1") (pinfunction "1_1") (pintype "passive"))
      (node (ref "R93") (pin "1") (pinfunction "1_1") (pintype "passive"))
      (node (ref "R94") (pin "1") (pinfunction "1_1") (pintype "passive"))
      (node (ref "T2") (pin "1") (pinfunction "S_1") (pintype "passive"))
      (node (ref "T2") (pin "4") (pinfunction "S_4") (pintype "passive"))
    )
    (net (code "62") (name "GND_VXCO") (class "Default")
      (node (ref "C110") (pin "2") (pinfunction "2_2") (pintype "passive"))
      (node (ref "C122") (pin "1") (pinfunction "1_1") (pintype "passive"))
      (node (ref "C123") (pin "1") (pinfunction "1_1") (pintype "passive"))
      (node (ref "C128") (pin "1") (pinfunction "1_1") (pintype "passive"))
      (node (ref "C135") (pin "1") (pinfunction "1_1") (pintype "passive"))
      (node (ref "C136") (pin "1") (pinfunction "1_1") (pintype "passive"))
      (node (ref "L26") (pin "1") (pinfunction "1_1") (pintype "passive"))
      (node (ref "OSC2") (pin "3") (pinfunction "GND_3") (pintype "power_in"))
    )
    (net (code "63") (name "Net-(C15-Pad2)") (class "Default")
      (node (ref "C15") (pin "2") (pinfunction "2_2") (pintype "passive"))
      (node (ref "R37") (pin "1") (pinfunction "1_1") (pintype "passive"))
    )
    (net (code "64") (name "Net-(C121-Pad2)") (class "Default")
      (node (ref "C121") (pin "2") (pinfunction "2_2") (pintype "passive"))
      (node (ref "R37") (pin "2") (pinfunction "2_2") (pintype "passive"))
      (node (ref "R58") (pin "2") (pinfunction "2_2") (pintype "passive"))
    )
    (net (code "65") (name "Net-(C125-Pad1)") (class "Default")
      (node (ref "C125") (pin "1") (pinfunction "1_1") (pintype "passive"))
      (node (ref "R38") (pin "2") (pinfunction "2_2") (pintype "passive"))
    )
    (net (code "66") (name "Net-(C127-Pad1)") (class "Default")
      (node (ref "C127") (pin "1") (pinfunction "1_1") (pintype "passive"))
      (node (ref "R39") (pin "2") (pinfunction "2_2") (pintype "passive"))
    )
    (net (code "67") (name "Net-(IC7-CLKIN0)") (class "Default")
      (node (ref "C100") (pin "2") (pinfunction "2_2") (pintype "passive"))
      (node (ref "IC7") (pin "37") (pinfunction "CLKIN0_37") (pintype "input"))
    )
    (net (code "68") (name "Net-(IC7-LDOBYP1)") (class "Default")
      (node (ref "C112") (pin "2") (pinfunction "2_2") (pintype "passive"))
      (node (ref "IC7") (pin "11") (pinfunction "LDOBYP1_11") (pintype "passive"))
    )
    (net (code "69") (name "Net-(IC7-LDOBYP2)") (class "Default")
      (node (ref "C113") (pin "2") (pinfunction "2_2") (pintype "passive"))
      (node (ref "IC7") (pin "12") (pinfunction "LDOBYP2_12") (pintype "passive"))
    )
    (net (code "70") (name "Net-(IC7-SYNC{slash}SYSREF_REQ)") (class "Default")
      (node (ref "IC7") (pin "6") (pinfunction "SYNC/SYSREF_REQ_6") (pintype "input"))
      (node (ref "R28") (pin "2") (pinfunction "2_2") (pintype "passive"))
    )
    (net (code "71") (name "Net-(IC7-~{CLKIN0})") (class "Default")
      (node (ref "C102") (pin "2") (pinfunction "2_2") (pintype "passive"))
      (node (ref "IC7") (pin "38") (pinfunction "~{CLKIN0}_38") (pintype "input"))
    )
    (net (code "72") (name "Net-(IC8-VEN)") (class "Default")
      (node (ref "IC8") (pin "4") (pinfunction "VEN_4") (pintype "input"))
      (node (ref "R59") (pin "1") (pinfunction "1_1") (pintype "passive"))
    )
    (net (code "73") (name "Net-(IC8-VIN)") (class "Default")
      (node (ref "C161") (pin "2") (pinfunction "2_2") (pintype "passive"))
      (node (ref "IC8") (pin "6") (pinfunction "VIN_6") (pintype "input"))
      (node (ref "L42") (pin "2") (pinfunction "2_2") (pintype "passive"))
      (node (ref "R59") (pin "2") (pinfunction "2_2") (pintype "passive"))
    )
    (net (code "74") (name "Net-(IC8-VOUT)") (class "Default")
      (node (ref "C162") (pin "2") (pinfunction "2_2") (pintype "passive"))
      (node (ref "IC8") (pin "1") (pinfunction "VOUT_1") (pintype "power_in"))
      (node (ref "L43") (pin "1") (pinfunction "1_1") (pintype "passive"))
    )
    (net (code "75") (name "Net-(IC9-EN)") (class "Default")
      (node (ref "C145") (pin "2") (pinfunction "2_2") (pintype "passive"))
      (node (ref "IC9") (pin "5") (pinfunction "EN_5") (pintype "input"))
      (node (ref "IC9") (pin "7") (pinfunction "IN_7") (pintype "input"))
      (node (ref "IC9") (pin "8") (pinfunction "IN_8") (pintype "input"))
      (node (ref "L39") (pin "2") (pinfunction "2_2") (pintype "passive"))
    )
    (net (code "76") (name "Net-(IC9-FB)") (class "Default")
      (node (ref "C142") (pin "1") (pinfunction "1_1") (pintype "passive"))
      (node (ref "IC9") (pin "3") (pinfunction "FB_3") (pintype "input"))
      (node (ref "R40") (pin "1") (pinfunction "1_1") (pintype "passive"))
      (node (ref "R41") (pin "2") (pinfunction "2_2") (pintype "passive"))
    )
    (net (code "77") (name "Net-(IC9-NR)") (class "Default")
      (node (ref "C146") (pin "2") (pinfunction "2_2") (pintype "passive"))
      (node (ref "IC9") (pin "6") (pinfunction "NR_6") (pintype "passive"))
    )
    (net (code "78") (name "Net-(OSC1-VDD)") (class "Default")
      (node (ref "C106") (pin "2") (pinfunction "2_2") (pintype "passive"))
      (node (ref "L7") (pin "2") (pinfunction "2_2") (pintype "passive"))
      (node (ref "OSC1") (pin "6") (pinfunction "VDD_6") (pintype "power_in"))
    )
    (net (code "79") (name "Net-(OSC2-OE)") (class "Default")
      (node (ref "OSC2") (pin "2") (pinfunction "OE_2") (pintype "passive"))
      (node (ref "R55") (pin "1") (pinfunction "1_1") (pintype "passive"))
    )
    (net (code "80") (name "Net-(OSC2-OUT)") (class "Default")
      (node (ref "C15") (pin "1") (pinfunction "1_1") (pintype "passive"))
      (node (ref "OSC2") (pin "4") (pinfunction "OUT_4") (pintype "output"))
    )
    (net (code "81") (name "P1V8") (class "Default")
      (node (ref "C185") (pin "2") (pinfunction "2_2") (pintype "passive"))
      (node (ref "C186") (pin "2") (pinfunction "2_2") (pintype "passive"))
      (node (ref "IC16") (pin "3") (pinfunction "VCCA_3") (pintype "power_in"))
      (node (ref "IC16") (pin "5") (pinfunction "2DIR_5") (pintype "input"))
      (node (ref "IC17") (pin "3") (pinfunction "VCCA_3") (pintype "power_in"))
      (node (ref "IC17") (pin "4") (pinfunction "1DIR_4") (pintype "input"))
    )
    (net (code "82") (name "P3V3_PLL_VXCO") (class "Default")
      (node (ref "C122") (pin "2") (pinfunction "2_2") (pintype "passive"))
      (node (ref "C123") (pin "2") (pinfunction "2_2") (pintype "passive"))
      (node (ref "C128") (pin "2") (pinfunction "2_2") (pintype "passive"))
      (node (ref "C135") (pin "2") (pinfunction "2_2") (pintype "passive"))
      (node (ref "C136") (pin "2") (pinfunction "2_2") (pintype "passive"))
      (node (ref "L43") (pin "2") (pinfunction "2_2") (pintype "passive"))
      (node (ref "OSC2") (pin "6") (pinfunction "VDD_6") (pintype "power_in"))
      (node (ref "R55") (pin "2") (pinfunction "2_2") (pintype "passive"))
    )
    (net (code "83") (name "P5V0") (class "Default")
      (node (ref "C160") (pin "2") (pinfunction "2_2") (pintype "passive"))
      (node (ref "C199") (pin "2") (pinfunction "2_2") (pintype "passive"))
      (node (ref "L39") (pin "1") (pinfunction "1_1") (pintype "passive"))
      (node (ref "L42") (pin "1") (pinfunction "1_1") (pintype "passive"))
    )
    (net (code "84") (name "PLL_VCC_BUF") (class "Default")
      (node (ref "L19") (pin "2") (pinfunction "2_2") (pintype "passive"))
    )
    (net (code "85") (name "PLL_VCC_CLKOUT_PLANE") (class "Default")
      (node (ref "C137") (pin "2") (pinfunction "2_2") (pintype "passive"))
      (node (ref "L14") (pin "2") (pinfunction "2_2") (pintype "passive"))
      (node (ref "L15") (pin "1") (pinfunction "1_1") (pintype "passive"))
      (node (ref "L16") (pin "1") (pinfunction "1_1") (pintype "passive"))
      (node (ref "L17") (pin "1") (pinfunction "1_1") (pintype "passive"))
      (node (ref "L18") (pin "1") (pinfunction "1_1") (pintype "passive"))
    )
    (net (code "86") (name "PLL_VCC_PLANE") (class "Default")
      (node (ref "C142") (pin "2") (pinfunction "2_2") (pintype "passive"))
      (node (ref "C143") (pin "2") (pinfunction "2_2") (pintype "passive"))
      (node (ref "C144") (pin "2") (pinfunction "2_2") (pintype "passive"))
      (node (ref "C183") (pin "2") (pinfunction "2_2") (pintype "passive"))
      (node (ref "C184") (pin "2") (pinfunction "2_2") (pintype "passive"))
      (node (ref "IC16") (pin "2") (pinfunction "VCCB_2") (pintype "power_in"))
      (node (ref "IC17") (pin "2") (pinfunction "VCCB_2") (pintype "power_in"))
      (node (ref "IC9") (pin "1") (pinfunction "OUT_1") (pintype "power_in"))
      (node (ref "IC9") (pin "2") (pinfunction "OUT_2") (pintype "power_in"))
      (node (ref "L13") (pin "1") (pinfunction "1_1") (pintype "passive"))
      (node (ref "L14") (pin "1") (pinfunction "1_1") (pintype "passive"))
      (node (ref "L19") (pin "1") (pinfunction "1_1") (pintype "passive"))
      (node (ref "L7") (pin "1") (pinfunction "1_1") (pintype "passive"))
      (node (ref "L9") (pin "1") (pinfunction "1_1") (pintype "passive"))
      (node (ref "R40") (pin "2") (pinfunction "2_2") (pintype "passive"))
      (node (ref "R91") (pin "2") (pinfunction "2_2") (pintype "passive"))
      (node (ref "R92") (pin "2") (pinfunction "2_2") (pintype "passive"))
    )
    (net (code "87") (name "PLL_VTUNE1") (class "Default")
      (node (ref "C110") (pin "1") (pinfunction "1_1") (pintype "passive"))
      (node (ref "C126") (pin "2") (pinfunction "2_2") (pintype "passive"))
      (node (ref "C127") (pin "2") (pinfunction "2_2") (pintype "passive"))
      (node (ref "IC7") (pin "32") (pinfunction "CPOUT1_32") (pintype "passive"))
      (node (ref "OSC2") (pin "1") (pinfunction "VC_1") (pintype "input"))
    )
    (net (code "88") (name "PLL_VTUNE2") (class "Default")
      (node (ref "C124") (pin "2") (pinfunction "2_2") (pintype "passive"))
      (node (ref "C125") (pin "2") (pinfunction "2_2") (pintype "passive"))
      (node (ref "IC7") (pin "46") (pinfunction "CPOUT2_46") (pintype "output"))
    )
    (net (code "89") (name "unconnected-(IC7-CLKIN2{slash}OSCOUT-Pad40)") (class "Default")
      (node (ref "IC7") (pin "40") (pinfunction "CLKIN2/OSCOUT_40") (pintype "bidirectional+no_connect"))
    )
    (net (code "90") (name "unconnected-(IC7-DCLKOUT0-Pad1)") (class "Default")
      (node (ref "IC7") (pin "1") (pinfunction "DCLKOUT0_1") (pintype "output+no_connect"))
    )
    (net (code "91") (name "unconnected-(IC7-DCLKOUT2-Pad15)") (class "Default")
      (node (ref "IC7") (pin "15") (pinfunction "DCLKOUT2_15") (pintype "output+no_connect"))
    )
    (net (code "92") (name "unconnected-(IC7-DCLKOUT4-Pad24)") (class "Default")
      (node (ref "IC7") (pin "24") (pinfunction "DCLKOUT4_24") (pintype "output+no_connect"))
    )
    (net (code "93") (name "unconnected-(IC7-DCLKOUT6-Pad27)") (class "Default")
      (node (ref "IC7") (pin "27") (pinfunction "DCLKOUT6_27") (pintype "output+no_connect"))
    )
    (net (code "94") (name "unconnected-(IC7-DCLKOUT8-Pad51)") (class "Default")
      (node (ref "IC7") (pin "51") (pinfunction "DCLKOUT8_51") (pintype "output+no_connect"))
    )
    (net (code "95") (name "unconnected-(IC7-DCLKOUT10-Pad54)") (class "Default")
      (node (ref "IC7") (pin "54") (pinfunction "DCLKOUT10_54") (pintype "output+no_connect"))
    )
    (net (code "96") (name "unconnected-(IC7-DCLKOUT12-Pad62)") (class "Default")
      (node (ref "IC7") (pin "62") (pinfunction "DCLKOUT12_62") (pintype "output+no_connect"))
    )
    (net (code "97") (name "unconnected-(IC7-NC-Pad7)") (class "Default")
      (node (ref "IC7") (pin "7") (pinfunction "NC_7") (pintype "passive+no_connect"))
    )
    (net (code "98") (name "unconnected-(IC7-NC-Pad8)") (class "Default")
      (node (ref "IC7") (pin "8") (pinfunction "NC_8") (pintype "passive+no_connect"))
    )
    (net (code "99") (name "unconnected-(IC7-NC-Pad9)") (class "Default")
      (node (ref "IC7") (pin "9") (pinfunction "NC_9") (pintype "passive+no_connect"))
    )
    (net (code "100") (name "unconnected-(IC7-SDCLKOUT7-Pad29)") (class "Default")
      (node (ref "IC7") (pin "29") (pinfunction "SDCLKOUT7_29") (pintype "input+no_connect"))
    )
    (net (code "101") (name "unconnected-(IC7-SDCLKOUT13-Pad60)") (class "Default")
      (node (ref "IC7") (pin "60") (pinfunction "SDCLKOUT13_60") (pintype "output+no_connect"))
    )
    (net (code "102") (name "unconnected-(IC7-~{CLKIN2}{slash}~{OSCOUT}-Pad41)") (class "Default")
      (node (ref "IC7") (pin "41") (pinfunction "~{CLKIN2}/~{OSCOUT}_41") (pintype "bidirectional+no_connect"))
    )
    (net (code "103") (name "unconnected-(IC7-~{DCLKOUT0}-Pad2)") (class "Default")
      (node (ref "IC7") (pin "2") (pinfunction "~{DCLKOUT0}_2") (pintype "output+no_connect"))
    )
    (net (code "104") (name "unconnected-(IC7-~{DCLKOUT2}-Pad16)") (class "Default")
      (node (ref "IC7") (pin "16") (pinfunction "~{DCLKOUT2}_16") (pintype "output+no_connect"))
    )
    (net (code "105") (name "unconnected-(IC7-~{DCLKOUT4}-Pad25)") (class "Default")
      (node (ref "IC7") (pin "25") (pinfunction "~{DCLKOUT4}_25") (pintype "output+no_connect"))
    )
    (net (code "106") (name "unconnected-(IC7-~{DCLKOUT6}-Pad28)") (class "Default")
      (node (ref "IC7") (pin "28") (pinfunction "~{DCLKOUT6}_28") (pintype "output+no_connect"))
    )
    (net (code "107") (name "unconnected-(IC7-~{DCLKOUT8}-Pad52)") (class "Default")
      (node (ref "IC7") (pin "52") (pinfunction "~{DCLKOUT8}_52") (pintype "output+no_connect"))
    )
    (net (code "108") (name "unconnected-(IC7-~{DCLKOUT10}-Pad55)") (class "Default")
      (node (ref "IC7") (pin "55") (pinfunction "~{DCLKOUT10}_55") (pintype "output+no_connect"))
    )
    (net (code "109") (name "unconnected-(IC7-~{DCLKOUT12}-Pad63)") (class "Default")
      (node (ref "IC7") (pin "63") (pinfunction "~{DCLKOUT12}_63") (pintype "output+no_connect"))
    )
    (net (code "110") (name "unconnected-(IC7-~{SDCLKOUT7}-Pad30)") (class "Default")
      (node (ref "IC7") (pin "30") (pinfunction "~{SDCLKOUT7}_30") (pintype "power_in+no_connect"))
    )
    (net (code "111") (name "unconnected-(IC7-~{SDCLKOUT13}-Pad61)") (class "Default")
      (node (ref "IC7") (pin "61") (pinfunction "~{SDCLKOUT13}_61") (pintype "output+no_connect"))
    )
    (net (code "112") (name "unconnected-(IC8-NC-Pad2)") (class "Default")
      (node (ref "IC8") (pin "2") (pinfunction "NC_2") (pintype "passive+no_connect"))
    )
    (net (code "113") (name "unconnected-(IC8-NC-Pad5)") (class "Default")
      (node (ref "IC8") (pin "5") (pinfunction "NC_5") (pintype "passive+no_connect"))
    )
    (net (code "114") (name "unconnected-(OSC1-NC-Pad2)") (class "Default")
      (node (ref "OSC1") (pin "2") (pinfunction "NC_2") (pintype "passive+no_connect"))
    )
    (net (code "115") (name "unconnected-(OSC2-~{OUT}-Pad5)") (class "Default")
      (node (ref "OSC2") (pin "5") (pinfunction "~{OUT}_5") (pintype "output+no_connect"))
    )
  )
)
